# board.net
KiCad netlist of a schematic drawn in EAGLE
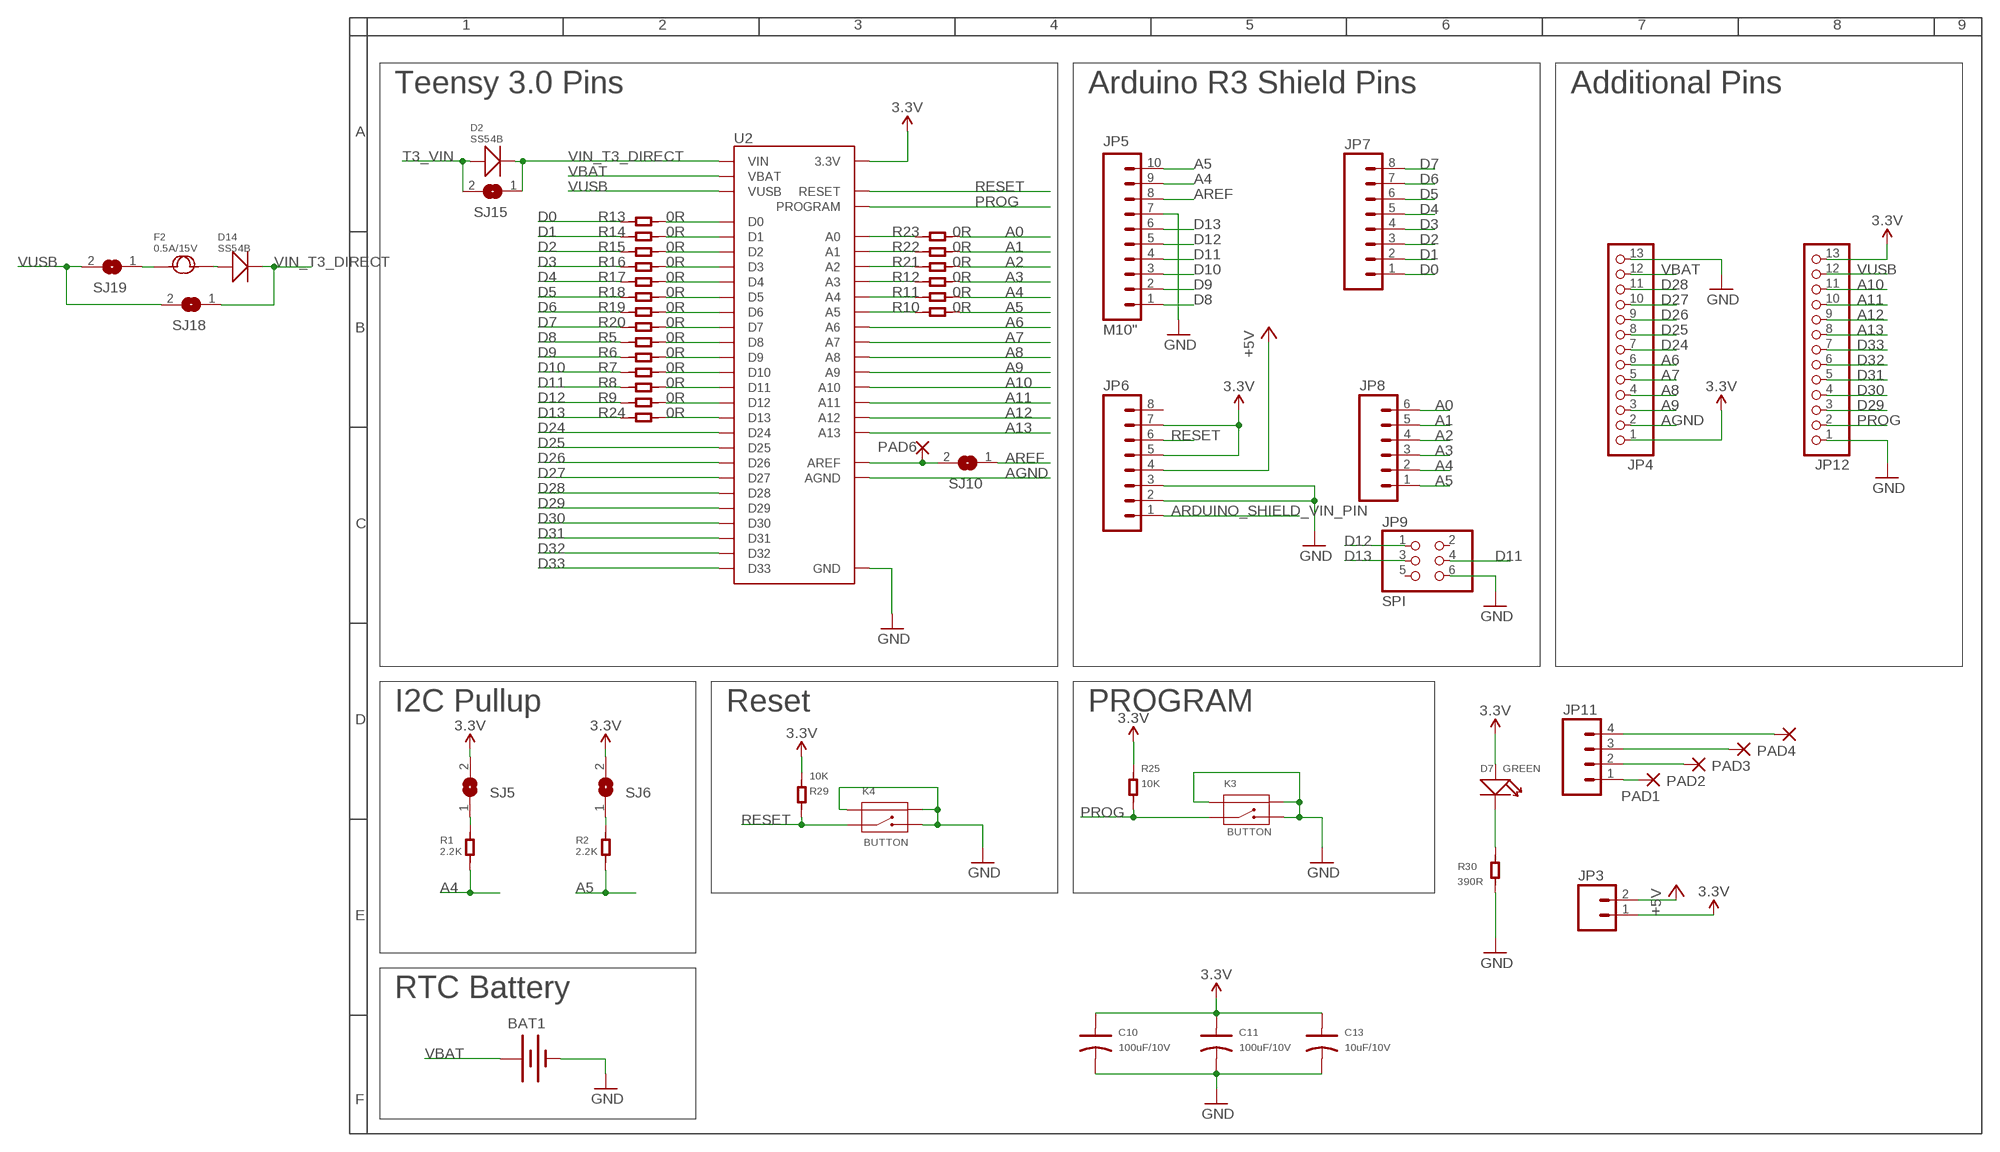
[diagram p0: schematic, sheet 1]
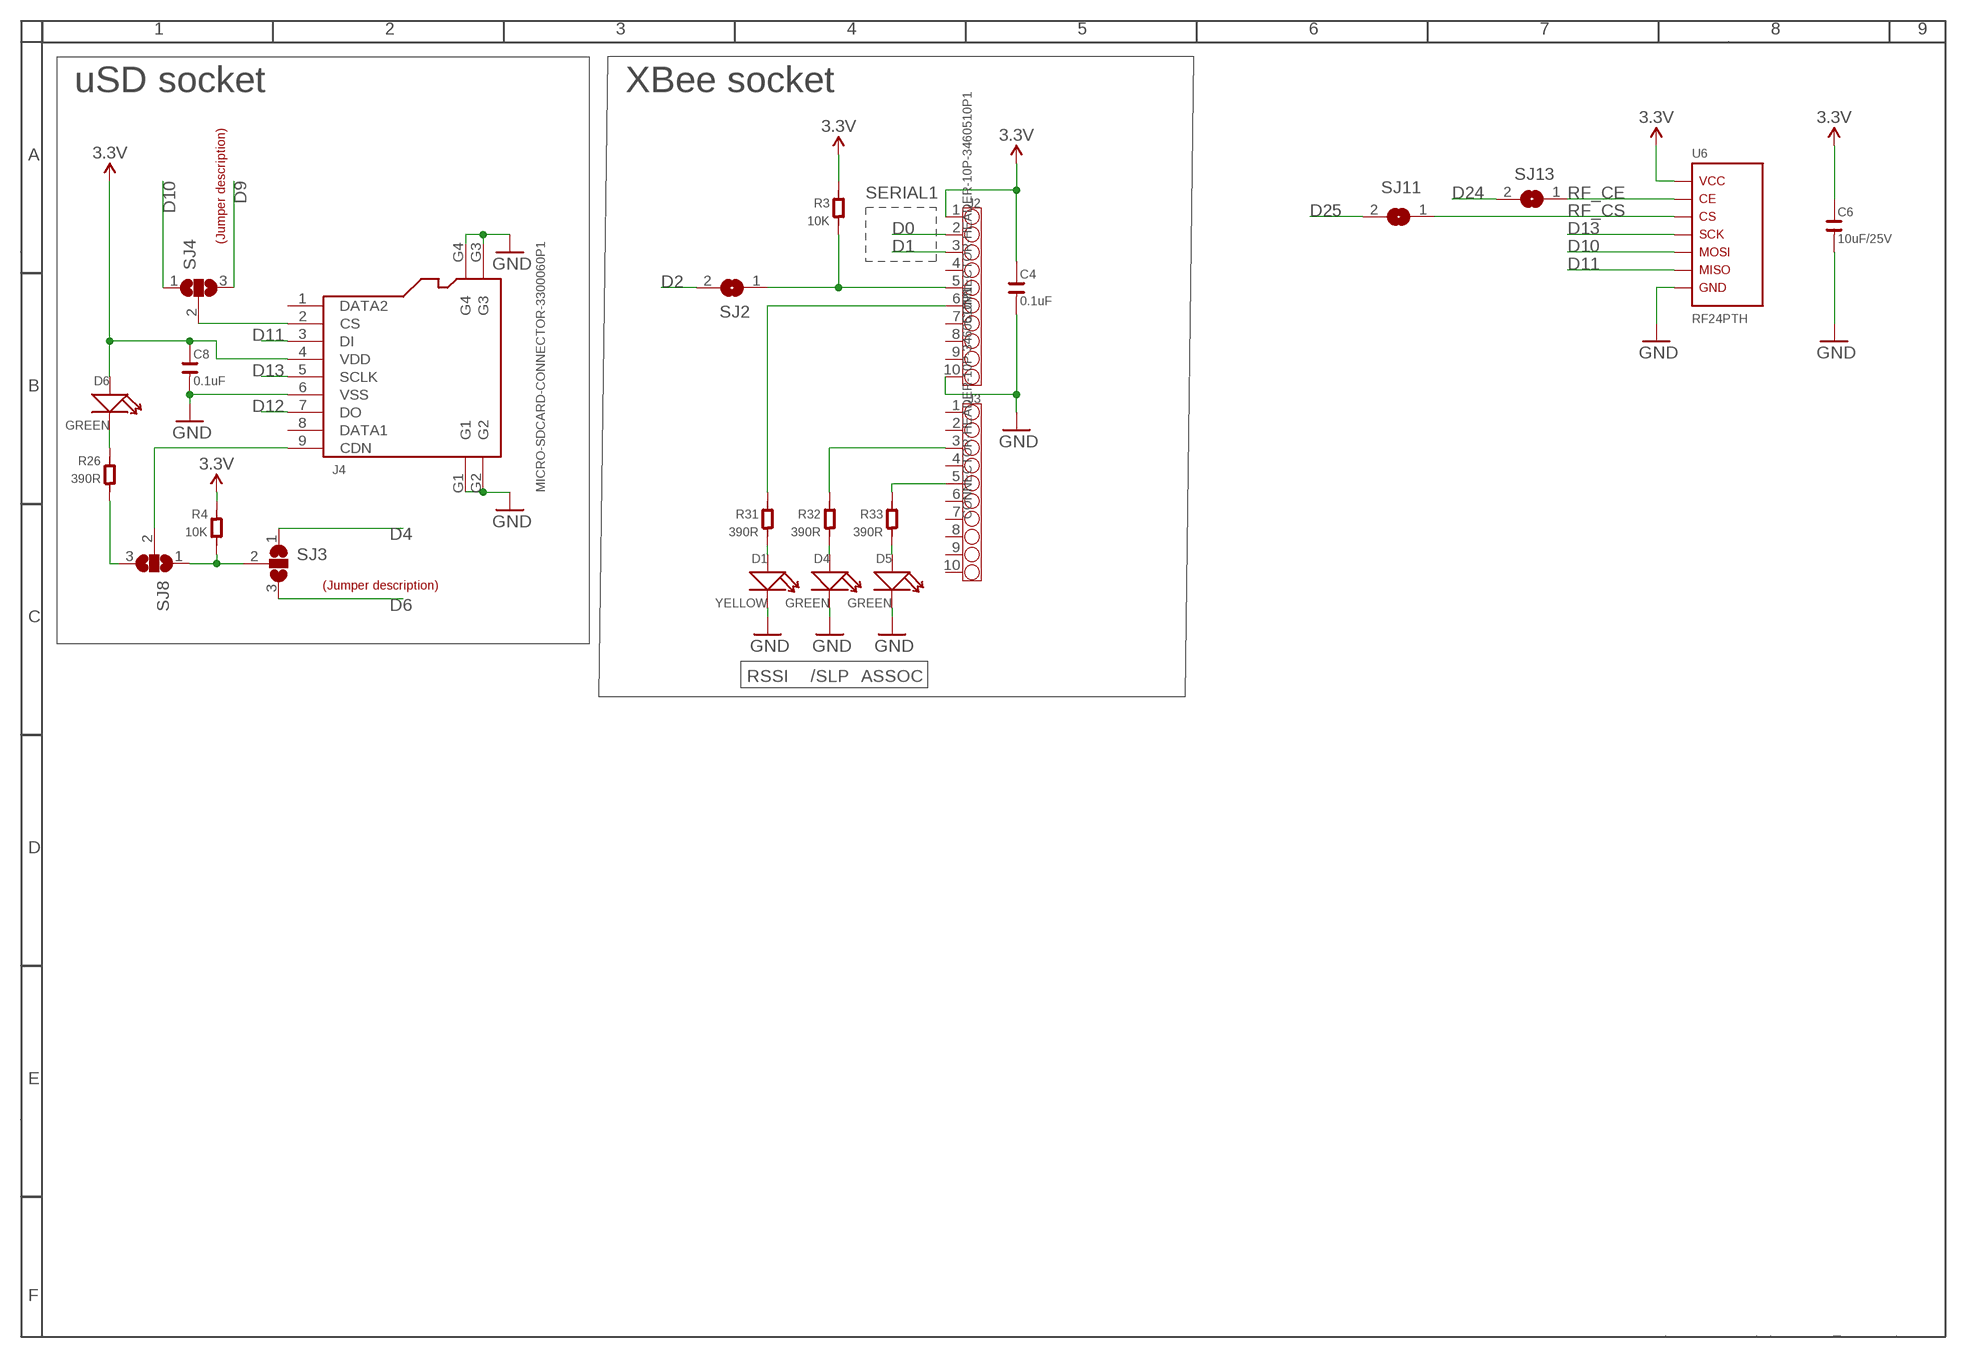
[diagram p1: schematic, sheet 2]
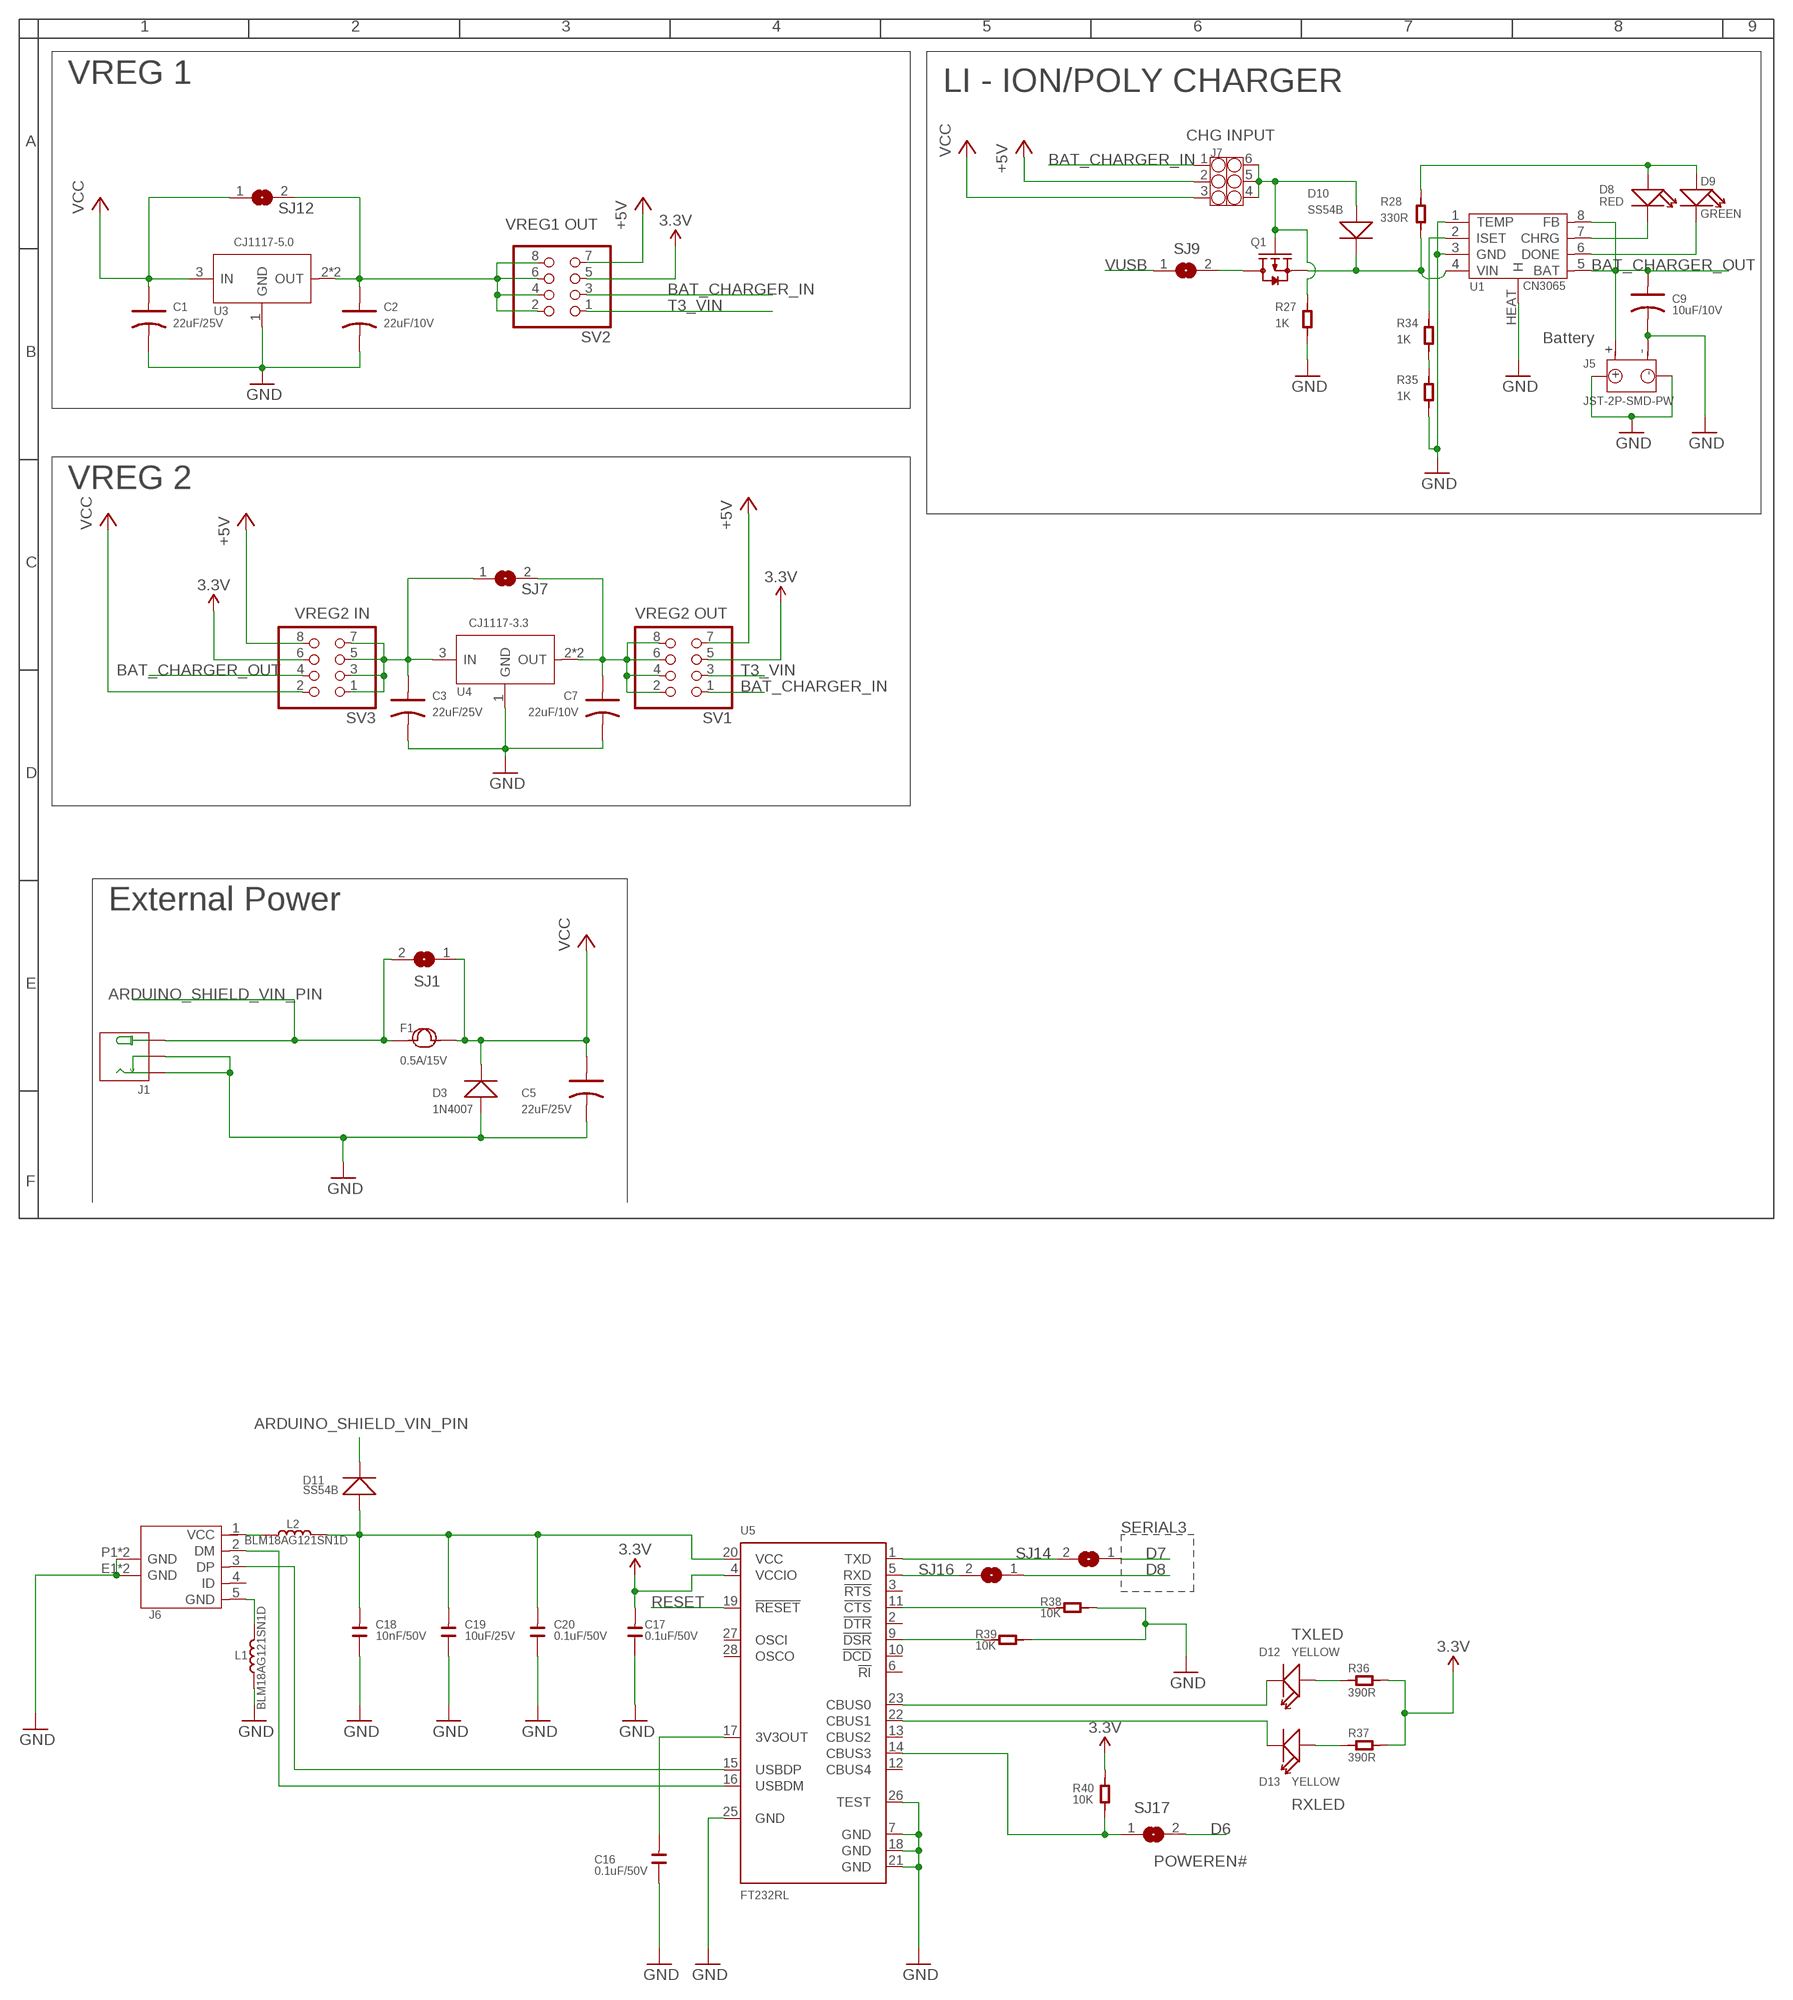
[diagram p2: schematic, sheet 3]

(export (version "E")
  (design (tool "Eeschema 10.0.6"))
  (components
    (comp (ref "C4")
      (value "0.1uF")
      (footprint "eagle-import:C0603")
      (libsource (lib "eagle-import") (part "C-0603"))
    )
    (comp (ref "C6")
      (value "10uF/25V")
      (footprint "eagle-import:C0805")
      (libsource (lib "eagle-import") (part "C-0805"))
    )
    (comp (ref "C8")
      (value "0.1uF")
      (footprint "eagle-import:C0603")
      (libsource (lib "eagle-import") (part "C-0603"))
    )
    (comp (ref "D1")
      (value "YELLOW")
      (footprint "eagle-import:LED0603")
      (libsource (lib "eagle-import") (part "LED"))
    )
    (comp (ref "D4")
      (value "GREEN")
      (footprint "eagle-import:LED0603")
      (libsource (lib "eagle-import") (part "LED"))
    )
    (comp (ref "D5")
      (value "GREEN")
      (footprint "eagle-import:LED0603")
      (libsource (lib "eagle-import") (part "LED"))
    )
    (comp (ref "D6")
      (value "GREEN")
      (footprint "eagle-import:LED0603")
      (libsource (lib "eagle-import") (part "LED"))
    )
    (comp (ref "J2")
      (value "CONNECTOR-HEADER-10P-3460510P1")
      (footprint "eagle-import:1X10P-2.0-4.3-BLUE-FEMALE")
      (libsource (lib "eagle-import") (part "CONNECTOR-HEADER-10P-3460510P1"))
    )
    (comp (ref "J3")
      (value "CONNECTOR-HEADER-10P-3460510P1")
      (footprint "eagle-import:1X10P-2.0-4.3-BLUE-FEMALE")
      (libsource (lib "eagle-import") (part "CONNECTOR-HEADER-10P-3460510P1"))
    )
    (comp (ref "J4")
      (value "MICRO-SDCARD-CONNECTOR-3300060P1")
      (footprint "eagle-import:9P-SMD-W-RING")
      (libsource (lib "eagle-import") (part "MICRO-SDCARD-CONNECTOR-3300060P1"))
    )
    (comp (ref "R3")
      (value "10K")
      (footprint "eagle-import:R0603")
      (libsource (lib "eagle-import") (part "R-0603"))
    )
    (comp (ref "R4")
      (value "10K")
      (footprint "eagle-import:R0603")
      (libsource (lib "eagle-import") (part "R-0603"))
    )
    (comp (ref "R26")
      (value "390R")
      (footprint "eagle-import:R0603")
      (libsource (lib "eagle-import") (part "R-0603"))
    )
    (comp (ref "R31")
      (value "390R")
      (footprint "eagle-import:R0603")
      (libsource (lib "eagle-import") (part "R-0603"))
    )
    (comp (ref "R32")
      (value "390R")
      (footprint "eagle-import:R0603")
      (libsource (lib "eagle-import") (part "R-0603"))
    )
    (comp (ref "R33")
      (value "390R")
      (footprint "eagle-import:R0603")
      (libsource (lib "eagle-import") (part "R-0603"))
    )
    (comp (ref "SJ2")
      (value "JUMPER_2WSMALL")
      (footprint "eagle-import:JUMPER_SMALL_2WAY")
      (libsource (lib "eagle-import") (part "JUMPER_2WSMALL"))
    )
    (comp (ref "SJ3")
      (value "SJ2W")
      (footprint "eagle-import:SJ_2")
      (libsource (lib "eagle-import") (part "SJ2W"))
    )
    (comp (ref "SJ4")
      (value "SJ2W")
      (footprint "eagle-import:SJ_2")
      (libsource (lib "eagle-import") (part "SJ2W"))
    )
    (comp (ref "SJ8")
      (value "SJ2W")
      (footprint "eagle-import:SJ_2")
      (libsource (lib "eagle-import") (part "SJ2W"))
    )
    (comp (ref "SJ11")
      (value "JUMPER_2WSMALL")
      (footprint "eagle-import:JUMPER_SMALL_2WAY")
      (libsource (lib "eagle-import") (part "JUMPER_2WSMALL"))
    )
    (comp (ref "SJ13")
      (value "JUMPER_2WSMALL")
      (footprint "eagle-import:JUMPER_SMALL_2WAY")
      (libsource (lib "eagle-import") (part "JUMPER_2WSMALL"))
    )
    (comp (ref "U$1")
      (value "LABEL_JUMPER_1X3")
      (footprint "eagle-import:JUMP3_DESC")
      (fields (field (name "LEFT") "D4") (field (name "RIGHT") "D6"))
      (libsource (lib "eagle-import") (part "LABEL_JUMPER_1X3"))
    )
    (comp (ref "U$2")
      (value "LABEL_JUMPER_1X3")
      (footprint "eagle-import:JUMP3_DESC")
      (fields (field (name "LEFT") "D9") (field (name "RIGHT") "D10"))
      (libsource (lib "eagle-import") (part "LABEL_JUMPER_1X3"))
    )
    (comp (ref "U6")
      (value "RF24PTH")
      (footprint "eagle-import:RF24")
      (libsource (lib "eagle-import") (part "RF24PTH"))
    )
    (comp (ref "BAT1")
      (value "BATTERY12MM")
      (footprint "eagle-import:BATTCON_12MM")
      (libsource (lib "eagle-import") (part "BATTERY12MM"))
    )
    (comp (ref "C10")
      (value "100uF/10V")
      (footprint "eagle-import:AVX-C")
      (libsource (lib "eagle-import") (part "C-POLAR-C"))
    )
    (comp (ref "C11")
      (value "100uF/10V")
      (footprint "eagle-import:AVX-C")
      (libsource (lib "eagle-import") (part "C-POLAR-C"))
    )
    (comp (ref "C13")
      (value "10uF/10V")
      (footprint "eagle-import:AVX-B")
      (libsource (lib "eagle-import") (part "C-POLAR-B"))
    )
    (comp (ref "D2")
      (value "SS54B")
      (footprint "eagle-import:SMB")
      (libsource (lib "eagle-import") (part "D-SMB"))
    )
    (comp (ref "D7")
      (value "GREEN")
      (footprint "eagle-import:LED0603")
      (libsource (lib "eagle-import") (part "LED"))
    )
    (comp (ref "D14")
      (value "SS54B")
      (footprint "eagle-import:SMB")
      (libsource (lib "eagle-import") (part "D-SMB"))
    )
    (comp (ref "F2")
      (value "0.5A/15V")
      (footprint "eagle-import:F1812")
      (libsource (lib "eagle-import") (part "OPL_20130807_FUSE-1812"))
    )
    (comp (ref "JP3")
      (value "M02PTH")
      (footprint "eagle-import:1X02")
      (libsource (lib "eagle-import") (part "M02PTH"))
    )
    (comp (ref "JP4")
      (value "PINHD-1X13_BIG")
      (footprint "eagle-import:1X13-BIG")
      (libsource (lib "eagle-import") (part "PINHD-1X13_BIG"))
    )
    (comp (ref "JP5")
      (value "M10\"")
      (footprint "eagle-import:1X10")
      (libsource (lib "eagle-import") (part "M10{dblquote}"))
    )
    (comp (ref "JP6")
      (value "M081X08")
      (footprint "eagle-import:1X08")
      (libsource (lib "eagle-import") (part "M081X08"))
    )
    (comp (ref "JP7")
      (value "M081X08")
      (footprint "eagle-import:1X08")
      (libsource (lib "eagle-import") (part "M081X08"))
    )
    (comp (ref "JP8")
      (value "M06SIP")
      (footprint "eagle-import:1X06")
      (libsource (lib "eagle-import") (part "M06SIP"))
    )
    (comp (ref "JP9")
      (value "SPI")
      (footprint "eagle-import:2X03")
      (libsource (lib "eagle-import") (part "PINHD-2X3"))
    )
    (comp (ref "JP11")
      (value "M04PTH")
      (footprint "eagle-import:1X04")
      (libsource (lib "eagle-import") (part "M04PTH"))
    )
    (comp (ref "JP12")
      (value "PINHD-1X13_BIG")
      (footprint "eagle-import:1X13-BIG")
      (libsource (lib "eagle-import") (part "PINHD-1X13_BIG"))
    )
    (comp (ref "K3")
      (value "BUTTON")
      (footprint "eagle-import:4P-SMD-7.0X3.5X3.5H-90D")
      (libsource (lib "eagle-import") (part "BUTTON-2P-REINFORCE-3100060P1"))
    )
    (comp (ref "K4")
      (value "BUTTON")
      (footprint "eagle-import:4P-SMD-7.0X3.5X3.5H-90D")
      (libsource (lib "eagle-import") (part "BUTTON-2P-REINFORCE-3100060P1"))
    )
    (comp (ref "PAD1")
      (value "WIREPADSMD1,27-254")
      (footprint "eagle-import:SMD1,27-2,54")
      (libsource (lib "eagle-import") (part "WIREPADSMD1,27-254"))
    )
    (comp (ref "PAD2")
      (value "WIREPADSMD1,27-254")
      (footprint "eagle-import:SMD1,27-2,54")
      (libsource (lib "eagle-import") (part "WIREPADSMD1,27-254"))
    )
    (comp (ref "PAD3")
      (value "WIREPADSMD1,27-254")
      (footprint "eagle-import:SMD1,27-2,54")
      (libsource (lib "eagle-import") (part "WIREPADSMD1,27-254"))
    )
    (comp (ref "PAD4")
      (value "WIREPADSMD1,27-254")
      (footprint "eagle-import:SMD1,27-2,54")
      (libsource (lib "eagle-import") (part "WIREPADSMD1,27-254"))
    )
    (comp (ref "PAD6")
      (value "AREF")
      (footprint "eagle-import:SMD1,27-2,54")
      (libsource (lib "eagle-import") (part "SMD2"))
    )
    (comp (ref "R1")
      (value "2.2K")
      (footprint "eagle-import:R0603")
      (libsource (lib "eagle-import") (part "R-0603"))
    )
    (comp (ref "R2")
      (value "2.2K")
      (footprint "eagle-import:R0603")
      (libsource (lib "eagle-import") (part "R-0603"))
    )
    (comp (ref "R5")
      (value "0R")
      (footprint "eagle-import:R0603")
      (libsource (lib "eagle-import") (part "R-0603"))
    )
    (comp (ref "R6")
      (value "0R")
      (footprint "eagle-import:R0603")
      (libsource (lib "eagle-import") (part "R-0603"))
    )
    (comp (ref "R7")
      (value "0R")
      (footprint "eagle-import:R0603")
      (libsource (lib "eagle-import") (part "R-0603"))
    )
    (comp (ref "R8")
      (value "0R")
      (footprint "eagle-import:R0603")
      (libsource (lib "eagle-import") (part "R-0603"))
    )
    (comp (ref "R9")
      (value "0R")
      (footprint "eagle-import:R0603")
      (libsource (lib "eagle-import") (part "R-0603"))
    )
    (comp (ref "R10")
      (value "0R")
      (footprint "eagle-import:R0603")
      (libsource (lib "eagle-import") (part "R-0603"))
    )
    (comp (ref "R11")
      (value "0R")
      (footprint "eagle-import:R0603")
      (libsource (lib "eagle-import") (part "R-0603"))
    )
    (comp (ref "R12")
      (value "0R")
      (footprint "eagle-import:R0603")
      (libsource (lib "eagle-import") (part "R-0603"))
    )
    (comp (ref "R13")
      (value "0R")
      (footprint "eagle-import:R0603")
      (libsource (lib "eagle-import") (part "R-0603"))
    )
    (comp (ref "R14")
      (value "0R")
      (footprint "eagle-import:R0603")
      (libsource (lib "eagle-import") (part "R-0603"))
    )
    (comp (ref "R15")
      (value "0R")
      (footprint "eagle-import:R0603")
      (libsource (lib "eagle-import") (part "R-0603"))
    )
    (comp (ref "R16")
      (value "0R")
      (footprint "eagle-import:R0603")
      (libsource (lib "eagle-import") (part "R-0603"))
    )
    (comp (ref "R17")
      (value "0R")
      (footprint "eagle-import:R0603")
      (libsource (lib "eagle-import") (part "R-0603"))
    )
    (comp (ref "R18")
      (value "0R")
      (footprint "eagle-import:R0603")
      (libsource (lib "eagle-import") (part "R-0603"))
    )
    (comp (ref "R19")
      (value "0R")
      (footprint "eagle-import:R0603")
      (libsource (lib "eagle-import") (part "R-0603"))
    )
    (comp (ref "R20")
      (value "0R")
      (footprint "eagle-import:R0603")
      (libsource (lib "eagle-import") (part "R-0603"))
    )
    (comp (ref "R21")
      (value "0R")
      (footprint "eagle-import:R0603")
      (libsource (lib "eagle-import") (part "R-0603"))
    )
    (comp (ref "R22")
      (value "0R")
      (footprint "eagle-import:R0603")
      (libsource (lib "eagle-import") (part "R-0603"))
    )
    (comp (ref "R23")
      (value "0R")
      (footprint "eagle-import:R0603")
      (libsource (lib "eagle-import") (part "R-0603"))
    )
    (comp (ref "R24")
      (value "0R")
      (footprint "eagle-import:R0603")
      (libsource (lib "eagle-import") (part "R-0603"))
    )
    (comp (ref "R25")
      (value "10K")
      (footprint "eagle-import:R0603")
      (libsource (lib "eagle-import") (part "R-0603"))
    )
    (comp (ref "R29")
      (value "10K")
      (footprint "eagle-import:R0603")
      (libsource (lib "eagle-import") (part "R-0603"))
    )
    (comp (ref "R30")
      (value "390R")
      (footprint "eagle-import:R0603")
      (libsource (lib "eagle-import") (part "R-0603"))
    )
    (comp (ref "SJ5")
      (value "JUMPER_2WLARGE")
      (footprint "eagle-import:JUMPER_LARGE_2WAY")
      (libsource (lib "eagle-import") (part "JUMPER_2WLARGE"))
    )
    (comp (ref "SJ6")
      (value "JUMPER_2WLARGE")
      (footprint "eagle-import:JUMPER_LARGE_2WAY")
      (libsource (lib "eagle-import") (part "JUMPER_2WLARGE"))
    )
    (comp (ref "SJ10")
      (value "JUMPER_2WLARGE")
      (footprint "eagle-import:JUMPER_LARGE_2WAY")
      (libsource (lib "eagle-import") (part "JUMPER_2WLARGE"))
    )
    (comp (ref "SJ15")
      (value "JUMPER_2WLARGE")
      (footprint "eagle-import:JUMPER_LARGE_2WAY")
      (libsource (lib "eagle-import") (part "JUMPER_2WLARGE"))
    )
    (comp (ref "SJ18")
      (value "JUMPER_2WLARGE")
      (footprint "eagle-import:JUMPER_LARGE_2WAY")
      (libsource (lib "eagle-import") (part "JUMPER_2WLARGE"))
    )
    (comp (ref "SJ19")
      (value "JUMPER_2WLARGE")
      (footprint "eagle-import:JUMPER_LARGE_2WAY")
      (libsource (lib "eagle-import") (part "JUMPER_2WLARGE"))
    )
    (comp (ref "U2")
      (value "TEENSY3.0_ALLPINSSILK")
      (footprint "eagle-import:TEENSY3.0_ALLPINS_SILK")
      (libsource (lib "eagle-import") (part "TEENSY3.0_ALLPINSSILK"))
    )
    (comp (ref "C1")
      (value "22uF/25V")
      (footprint "eagle-import:AVX-C")
      (fields (field (name "MPN") "TAJC226K025RNJ"))
      (libsource (lib "eagle-import") (part "C-POLAR-C"))
    )
    (comp (ref "C2")
      (value "22uF/10V")
      (footprint "eagle-import:AVX-B")
      (libsource (lib "eagle-import") (part "C-POLAR-B"))
    )
    (comp (ref "C3")
      (value "22uF/25V")
      (footprint "eagle-import:AVX-C")
      (fields (field (name "MPN") "TAJC226K025RNJ"))
      (libsource (lib "eagle-import") (part "C-POLAR-C"))
    )
    (comp (ref "C5")
      (value "22uF/25V")
      (footprint "eagle-import:AVX-C")
      (libsource (lib "eagle-import") (part "C-POLAR-C"))
    )
    (comp (ref "C7")
      (value "22uF/10V")
      (footprint "eagle-import:AVX-B")
      (libsource (lib "eagle-import") (part "C-POLAR-B"))
    )
    (comp (ref "C9")
      (value "10uF/10V")
      (footprint "eagle-import:AVX-A")
      (libsource (lib "eagle-import") (part "C-POLAR-A"))
    )
    (comp (ref "C16")
      (value "0.1uF/50V")
      (footprint "eagle-import:C0603")
      (libsource (lib "eagle-import") (part "C-0603"))
    )
    (comp (ref "C17")
      (value "0.1uF/50V")
      (footprint "eagle-import:C0603")
      (libsource (lib "eagle-import") (part "C-0603"))
    )
    (comp (ref "C18")
      (value "10nF/50V")
      (footprint "eagle-import:C0603")
      (libsource (lib "eagle-import") (part "C-0603"))
    )
    (comp (ref "C19")
      (value "10uF/25V")
      (footprint "eagle-import:C0805")
      (libsource (lib "eagle-import") (part "C-0805"))
    )
    (comp (ref "C20")
      (value "0.1uF/50V")
      (footprint "eagle-import:C0603")
      (libsource (lib "eagle-import") (part "C-0603"))
    )
    (comp (ref "D3")
      (value "1N4007")
      (footprint "eagle-import:DO-214AC")
      (libsource (lib "eagle-import") (part "D-SMA"))
    )
    (comp (ref "D8")
      (value "RED")
      (footprint "eagle-import:LED0603")
      (libsource (lib "eagle-import") (part "LED"))
    )
    (comp (ref "D9")
      (value "GREEN")
      (footprint "eagle-import:LED0603")
      (libsource (lib "eagle-import") (part "LED"))
    )
    (comp (ref "D10")
      (value "SS54B")
      (footprint "eagle-import:SMB")
      (libsource (lib "eagle-import") (part "D-SMB"))
    )
    (comp (ref "D11")
      (value "SS54B")
      (footprint "eagle-import:SMB")
      (libsource (lib "eagle-import") (part "D-SMB"))
    )
    (comp (ref "D12")
      (value "YELLOW")
      (footprint "eagle-import:LED0603")
      (libsource (lib "eagle-import") (part "LED"))
    )
    (comp (ref "D13")
      (value "YELLOW")
      (footprint "eagle-import:LED0603")
      (libsource (lib "eagle-import") (part "LED"))
    )
    (comp (ref "F1")
      (value "0.5A/15V")
      (footprint "eagle-import:F1812")
      (libsource (lib "eagle-import") (part "FUSE-1812"))
    )
    (comp (ref "J1")
      (value "JACK-DC-3P-3410020P1")
      (footprint "eagle-import:PW-3P-2.1")
      (libsource (lib "eagle-import") (part "JACK-DC-3P-3410020P1"))
    )
    (comp (ref "J5")
      (value "JST-2P-SMD-PW")
      (footprint "eagle-import:2P-SMD-2.0-90D")
      (libsource (lib "eagle-import") (part "JST-2P-SMD-PW-3410050P1"))
    )
    (comp (ref "J6")
      (value "MICRO-USB-5P-3400150P1")
      (footprint "eagle-import:B-SMD-5P")
      (libsource (lib "eagle-import") (part "MICRO-USB-5P-3400150P1"))
    )
    (comp (ref "J7")
      (value "CONNECTOR-HEADER-2X3P-3460180P1")
      (footprint "eagle-import:2X3P-2.54-2.54-11.6-3.0-BLACK-MALE")
      (libsource (lib "eagle-import") (part "CONNECTOR-HEADER-2X3P-3460180P1"))
    )
    (comp (ref "L1")
      (value "BLM18AG121SN1D")
      (footprint "eagle-import:L0603")
      (libsource (lib "eagle-import") (part "L-0603"))
    )
    (comp (ref "L2")
      (value "BLM18AG121SN1D")
      (footprint "eagle-import:L0603")
      (libsource (lib "eagle-import") (part "L-0603"))
    )
    (comp (ref "Q1")
      (value "MOSFET-P-0440210P1")
      (footprint "eagle-import:SOT23")
      (libsource (lib "eagle-import") (part "MOSFET-P-0440210P1"))
    )
    (comp (ref "R27")
      (value "1K")
      (footprint "eagle-import:R0603")
      (libsource (lib "eagle-import") (part "R-0603"))
    )
    (comp (ref "R28")
      (value "330R")
      (footprint "eagle-import:R0603")
      (libsource (lib "eagle-import") (part "R-0603"))
    )
    (comp (ref "R34")
      (value "1K")
      (footprint "eagle-import:R0603")
      (libsource (lib "eagle-import") (part "R-0603"))
    )
    (comp (ref "R35")
      (value "1K")
      (footprint "eagle-import:R0603")
      (libsource (lib "eagle-import") (part "R-0603"))
    )
    (comp (ref "R36")
      (value "390R")
      (footprint "eagle-import:R0603")
      (libsource (lib "eagle-import") (part "R-0603"))
    )
    (comp (ref "R37")
      (value "390R")
      (footprint "eagle-import:R0603")
      (libsource (lib "eagle-import") (part "R-0603"))
    )
    (comp (ref "R38")
      (value "10K")
      (footprint "eagle-import:R0603")
      (libsource (lib "eagle-import") (part "R-0603"))
    )
    (comp (ref "R39")
      (value "10K")
      (footprint "eagle-import:R0603")
      (libsource (lib "eagle-import") (part "R-0603"))
    )
    (comp (ref "R40")
      (value "10K")
      (footprint "eagle-import:R0603")
      (libsource (lib "eagle-import") (part "R-0603"))
    )
    (comp (ref "SJ1")
      (value "JUMPER_2WLARGE")
      (footprint "eagle-import:JUMPER_LARGE_2WAY")
      (libsource (lib "eagle-import") (part "JUMPER_2WLARGE"))
    )
    (comp (ref "SJ7")
      (value "JUMPER_2WLARGE")
      (footprint "eagle-import:JUMPER_LARGE_2WAY")
      (libsource (lib "eagle-import") (part "JUMPER_2WLARGE"))
    )
    (comp (ref "SJ9")
      (value "JUMPER_2WLARGE")
      (footprint "eagle-import:JUMPER_LARGE_2WAY")
      (libsource (lib "eagle-import") (part "JUMPER_2WLARGE"))
    )
    (comp (ref "SJ12")
      (value "JUMPER_2WLARGE")
      (footprint "eagle-import:JUMPER_LARGE_2WAY")
      (libsource (lib "eagle-import") (part "JUMPER_2WLARGE"))
    )
    (comp (ref "SJ14")
      (value "JUMPER_2WLARGE")
      (footprint "eagle-import:JUMPER_LARGE_2WAY")
      (libsource (lib "eagle-import") (part "JUMPER_2WLARGE"))
    )
    (comp (ref "SJ16")
      (value "JUMPER_2WLARGE")
      (footprint "eagle-import:JUMPER_LARGE_2WAY")
      (libsource (lib "eagle-import") (part "JUMPER_2WLARGE"))
    )
    (comp (ref "SJ17")
      (value "JUMPER_2WLARGE")
      (footprint "eagle-import:JUMPER_LARGE_2WAY")
      (libsource (lib "eagle-import") (part "JUMPER_2WLARGE"))
    )
    (comp (ref "SV1")
      (value "PINHD-2X4_2.54")
      (footprint "eagle-import:2X04")
      (libsource (lib "eagle-import") (part "PINHD-2X4_2.54"))
    )
    (comp (ref "SV2")
      (value "PINHD-2X4_2.54")
      (footprint "eagle-import:2X04")
      (libsource (lib "eagle-import") (part "PINHD-2X4_2.54"))
    )
    (comp (ref "SV3")
      (value "PINHD-2X4_2.54")
      (footprint "eagle-import:2X04")
      (libsource (lib "eagle-import") (part "PINHD-2X4_2.54"))
    )
    (comp (ref "U1")
      (value "CN3065")
      (footprint "eagle-import:DFN8")
      (libsource (lib "eagle-import") (part "CN3065-1320040P1"))
    )
    (comp (ref "U3")
      (value "CJ1117-5.0")
      (footprint "eagle-import:SOT223")
      (libsource (lib "eagle-import") (part "CJ1117-5.0-1310170P1"))
    )
    (comp (ref "U4")
      (value "CJ1117-3.3")
      (footprint "eagle-import:SOT223")
      (libsource (lib "eagle-import") (part "CJ1117-3.3-1310190P1"))
    )
    (comp (ref "U5")
      (value "FT232RL")
      (footprint "eagle-import:SSOP28")
      (libsource (lib "eagle-import") (part "FT232RL-1720010P1"))
    )
  )
  (nets
    (net (code "1") (name "+5V") (class "Default")
      (node (ref "J7") (pin "2") (pinfunction "2_2") (pintype "bidirectional"))
      (node (ref "JP3") (pin "2") (pinfunction "2_2") (pintype "passive"))
      (node (ref "JP6") (pin "4") (pinfunction "4_4") (pintype "passive"))
      (node (ref "SV1") (pin "7") (pinfunction "7_7") (pintype "passive"))
      (node (ref "SV2") (pin "7") (pinfunction "7_7") (pintype "passive"))
      (node (ref "SV3") (pin "8") (pinfunction "8_8") (pintype "passive"))
    )
    (net (code "2") (name "3.3V") (class "Default")
      (node (ref "C10") (pin "+") (pinfunction "1_+") (pintype "bidirectional"))
      (node (ref "C11") (pin "+") (pinfunction "1_+") (pintype "bidirectional"))
      (node (ref "C13") (pin "+") (pinfunction "1_+") (pintype "bidirectional"))
      (node (ref "C17") (pin "1") (pinfunction "1_1") (pintype "bidirectional"))
      (node (ref "C4") (pin "2") (pinfunction "2_2") (pintype "bidirectional"))
      (node (ref "C6") (pin "2") (pinfunction "2_2") (pintype "bidirectional"))
      (node (ref "C8") (pin "2") (pinfunction "2_2") (pintype "bidirectional"))
      (node (ref "D6") (pin "+") (pinfunction "+_+") (pintype "passive"))
      (node (ref "D7") (pin "+") (pinfunction "+_+") (pintype "passive"))
      (node (ref "J2") (pin "1") (pinfunction "1_1") (pintype "bidirectional"))
      (node (ref "J4") (pin "4") (pinfunction "VDD_4") (pintype "bidirectional"))
      (node (ref "JP12") (pin "13") (pinfunction "13_13") (pintype "passive"))
      (node (ref "JP3") (pin "1") (pinfunction "1_1") (pintype "passive"))
      (node (ref "JP4") (pin "1") (pinfunction "1_1") (pintype "passive"))
      (node (ref "JP6") (pin "5") (pinfunction "5_5") (pintype "passive"))
      (node (ref "JP6") (pin "7") (pinfunction "7_7") (pintype "passive"))
      (node (ref "R25") (pin "2") (pinfunction "2_2") (pintype "bidirectional"))
      (node (ref "R29") (pin "2") (pinfunction "2_2") (pintype "bidirectional"))
      (node (ref "R3") (pin "2") (pinfunction "2_2") (pintype "bidirectional"))
      (node (ref "R36") (pin "2") (pinfunction "2_2") (pintype "bidirectional"))
      (node (ref "R37") (pin "2") (pinfunction "2_2") (pintype "bidirectional"))
      (node (ref "R4") (pin "1") (pinfunction "1_1") (pintype "bidirectional"))
      (node (ref "R40") (pin "2") (pinfunction "2_2") (pintype "bidirectional"))
      (node (ref "SJ5") (pin "2") (pinfunction "2_2") (pintype "passive"))
      (node (ref "SJ6") (pin "2") (pinfunction "2_2") (pintype "passive"))
      (node (ref "SV1") (pin "5") (pinfunction "5_5") (pintype "passive"))
      (node (ref "SV2") (pin "5") (pinfunction "5_5") (pintype "passive"))
      (node (ref "SV3") (pin "6") (pinfunction "6_6") (pintype "passive"))
      (node (ref "U2") (pin "3V3_A") (pinfunction "3.3V_3V3_A") (pintype "power_in"))
      (node (ref "U2") (pin "3V3_B") (pinfunction "3.3V_3V3_B") (pintype "power_in"))
      (node (ref "U2") (pin "3V3_C") (pinfunction "3.3V_3V3_C") (pintype "power_in"))
      (node (ref "U5") (pin "4") (pinfunction "VCCIO_4") (pintype "input"))
      (node (ref "U6") (pin "VCC") (pinfunction "VCC_VCC") (pintype "power_in"))
    )
    (net (code "3") (name "A0") (class "Default")
      (node (ref "JP8") (pin "6") (pinfunction "6_6") (pintype "passive"))
      (node (ref "R23") (pin "1") (pinfunction "1_1") (pintype "bidirectional"))
    )
    (net (code "4") (name "A1") (class "Default")
      (node (ref "JP8") (pin "5") (pinfunction "5_5") (pintype "passive"))
      (node (ref "R22") (pin "1") (pinfunction "1_1") (pintype "bidirectional"))
    )
    (net (code "5") (name "A2") (class "Default")
      (node (ref "JP8") (pin "4") (pinfunction "4_4") (pintype "passive"))
      (node (ref "R21") (pin "1") (pinfunction "1_1") (pintype "bidirectional"))
    )
    (net (code "6") (name "A3") (class "Default")
      (node (ref "JP8") (pin "3") (pinfunction "3_3") (pintype "passive"))
      (node (ref "R12") (pin "1") (pinfunction "1_1") (pintype "bidirectional"))
    )
    (net (code "7") (name "A4") (class "Default")
      (node (ref "JP5") (pin "9") (pinfunction "9_9") (pintype "passive"))
      (node (ref "JP8") (pin "2") (pinfunction "2_2") (pintype "passive"))
      (node (ref "R1") (pin "1") (pinfunction "1_1") (pintype "bidirectional"))
      (node (ref "R11") (pin "1") (pinfunction "1_1") (pintype "bidirectional"))
    )
    (net (code "8") (name "A5") (class "Default")
      (node (ref "JP5") (pin "10") (pinfunction "10_10") (pintype "passive"))
      (node (ref "JP8") (pin "1") (pinfunction "1_1") (pintype "passive"))
      (node (ref "R10") (pin "1") (pinfunction "1_1") (pintype "bidirectional"))
      (node (ref "R2") (pin "1") (pinfunction "1_1") (pintype "bidirectional"))
    )
    (net (code "9") (name "A6") (class "Default")
      (node (ref "JP4") (pin "6") (pinfunction "6_6") (pintype "passive"))
      (node (ref "U2") (pin "A6") (pinfunction "A6_A6") (pintype "bidirectional"))
    )
    (net (code "10") (name "A7") (class "Default")
      (node (ref "JP4") (pin "5") (pinfunction "5_5") (pintype "passive"))
      (node (ref "U2") (pin "A7") (pinfunction "A7_A7") (pintype "bidirectional"))
    )
    (net (code "11") (name "A8") (class "Default")
      (node (ref "JP4") (pin "4") (pinfunction "4_4") (pintype "passive"))
      (node (ref "U2") (pin "A8") (pinfunction "A8_A8") (pintype "bidirectional"))
    )
    (net (code "12") (name "A9") (class "Default")
      (node (ref "JP4") (pin "3") (pinfunction "3_3") (pintype "passive"))
      (node (ref "U2") (pin "A9") (pinfunction "A9_A9") (pintype "bidirectional"))
    )
    (net (code "13") (name "A10") (class "Default")
      (node (ref "JP12") (pin "11") (pinfunction "11_11") (pintype "passive"))
      (node (ref "U2") (pin "A10") (pinfunction "A10_A10") (pintype "bidirectional"))
    )
    (net (code "14") (name "A11") (class "Default")
      (node (ref "JP12") (pin "10") (pinfunction "10_10") (pintype "passive"))
      (node (ref "U2") (pin "A11") (pinfunction "A11_A11") (pintype "bidirectional"))
    )
    (net (code "15") (name "A12") (class "Default")
      (node (ref "JP12") (pin "9") (pinfunction "9_9") (pintype "passive"))
      (node (ref "U2") (pin "A12") (pinfunction "A12_A12") (pintype "bidirectional"))
    )
    (net (code "16") (name "A13") (class "Default")
      (node (ref "JP12") (pin "8") (pinfunction "8_8") (pintype "passive"))
      (node (ref "U2") (pin "A13") (pinfunction "A13_A13") (pintype "bidirectional"))
    )
    (net (code "17") (name "AGND") (class "Default")
      (node (ref "JP4") (pin "2") (pinfunction "2_2") (pintype "passive"))
      (node (ref "U2") (pin "AGND") (pinfunction "AGND_AGND") (pintype "bidirectional"))
    )
    (net (code "18") (name "ARDUINO_SHIELD_VIN_PIN") (class "Default")
      (node (ref "D11") (pin "-") (pinfunction "-_-") (pintype "passive"))
      (node (ref "F1") (pin "1") (pinfunction "1_1") (pintype "bidirectional"))
      (node (ref "J1") (pin "+") (pinfunction "+_+") (pintype "bidirectional"))
      (node (ref "JP6") (pin "1") (pinfunction "1_1") (pintype "passive"))
      (node (ref "SJ1") (pin "2") (pinfunction "2_2") (pintype "passive"))
    )
    (net (code "19") (name "AREF") (class "Default")
      (node (ref "JP5") (pin "8") (pinfunction "8_8") (pintype "passive"))
      (node (ref "SJ10") (pin "1") (pinfunction "1_1") (pintype "passive"))
    )
    (net (code "20") (name "BAT_CHARGER_IN") (class "Default")
      (node (ref "J7") (pin "1") (pinfunction "1_1") (pintype "bidirectional"))
      (node (ref "SV1") (pin "1") (pinfunction "1_1") (pintype "passive"))
      (node (ref "SV2") (pin "3") (pinfunction "3_3") (pintype "passive"))
    )
    (net (code "21") (name "BAT_CHARGER_OUT") (class "Default")
      (node (ref "C9") (pin "+") (pinfunction "1_+") (pintype "bidirectional"))
      (node (ref "J5") (pin "+") (pinfunction "+_+") (pintype "bidirectional"))
      (node (ref "SV3") (pin "4") (pinfunction "4_4") (pintype "passive"))
      (node (ref "U1") (pin "5") (pinfunction "BAT_5") (pintype "bidirectional"))
      (node (ref "U1") (pin "8") (pinfunction "FB_8") (pintype "input"))
    )
    (net (code "22") (name "D0") (class "Default")
      (node (ref "J2") (pin "2") (pinfunction "2_2") (pintype "bidirectional"))
      (node (ref "JP7") (pin "1") (pinfunction "1_1") (pintype "passive"))
      (node (ref "R13") (pin "2") (pinfunction "2_2") (pintype "bidirectional"))
    )
    (net (code "23") (name "D1") (class "Default")
      (node (ref "J2") (pin "3") (pinfunction "3_3") (pintype "bidirectional"))
      (node (ref "JP7") (pin "2") (pinfunction "2_2") (pintype "passive"))
      (node (ref "R14") (pin "2") (pinfunction "2_2") (pintype "bidirectional"))
    )
    (net (code "24") (name "D2") (class "Default")
      (node (ref "JP7") (pin "3") (pinfunction "3_3") (pintype "passive"))
      (node (ref "R15") (pin "2") (pinfunction "2_2") (pintype "bidirectional"))
      (node (ref "SJ2") (pin "2") (pinfunction "2_2") (pintype "passive"))
    )
    (net (code "25") (name "D3") (class "Default")
      (node (ref "JP7") (pin "4") (pinfunction "4_4") (pintype "passive"))
      (node (ref "R16") (pin "2") (pinfunction "2_2") (pintype "bidirectional"))
    )
    (net (code "26") (name "D4") (class "Default")
      (node (ref "JP7") (pin "5") (pinfunction "5_5") (pintype "passive"))
      (node (ref "R17") (pin "2") (pinfunction "2_2") (pintype "bidirectional"))
      (node (ref "SJ3") (pin "1") (pinfunction "1_1") (pintype "passive"))
    )
    (net (code "27") (name "D5") (class "Default")
      (node (ref "JP7") (pin "6") (pinfunction "6_6") (pintype "passive"))
      (node (ref "R18") (pin "2") (pinfunction "2_2") (pintype "bidirectional"))
    )
    (net (code "28") (name "D6") (class "Default")
      (node (ref "JP7") (pin "7") (pinfunction "7_7") (pintype "passive"))
      (node (ref "R19") (pin "2") (pinfunction "2_2") (pintype "bidirectional"))
      (node (ref "SJ17") (pin "2") (pinfunction "2_2") (pintype "passive"))
      (node (ref "SJ3") (pin "3") (pinfunction "3_3") (pintype "passive"))
    )
    (net (code "29") (name "D7") (class "Default")
      (node (ref "JP7") (pin "8") (pinfunction "8_8") (pintype "passive"))
      (node (ref "R20") (pin "2") (pinfunction "2_2") (pintype "bidirectional"))
      (node (ref "SJ14") (pin "1") (pinfunction "1_1") (pintype "passive"))
    )
    (net (code "30") (name "D8") (class "Default")
      (node (ref "JP5") (pin "1") (pinfunction "1_1") (pintype "passive"))
      (node (ref "R5") (pin "2") (pinfunction "2_2") (pintype "bidirectional"))
      (node (ref "SJ16") (pin "1") (pinfunction "1_1") (pintype "passive"))
    )
    (net (code "31") (name "D9") (class "Default")
      (node (ref "JP5") (pin "2") (pinfunction "2_2") (pintype "passive"))
      (node (ref "R6") (pin "2") (pinfunction "2_2") (pintype "bidirectional"))
      (node (ref "SJ4") (pin "3") (pinfunction "3_3") (pintype "passive"))
    )
    (net (code "32") (name "D10") (class "Default")
      (node (ref "JP5") (pin "3") (pinfunction "3_3") (pintype "passive"))
      (node (ref "R7") (pin "2") (pinfunction "2_2") (pintype "bidirectional"))
      (node (ref "SJ4") (pin "1") (pinfunction "1_1") (pintype "passive"))
      (node (ref "U6") (pin "MOSI") (pinfunction "MOSI_MOSI") (pintype "input"))
    )
    (net (code "33") (name "D11") (class "Default")
      (node (ref "J4") (pin "3") (pinfunction "DI_3") (pintype "bidirectional"))
      (node (ref "JP5") (pin "4") (pinfunction "4_4") (pintype "passive"))
      (node (ref "JP9") (pin "4") (pinfunction "4_4") (pintype "passive"))
      (node (ref "R8") (pin "2") (pinfunction "2_2") (pintype "bidirectional"))
      (node (ref "U6") (pin "MISO") (pinfunction "MISO_MISO") (pintype "output"))
    )
    (net (code "34") (name "D12") (class "Default")
      (node (ref "J4") (pin "7") (pinfunction "DO_7") (pintype "bidirectional"))
      (node (ref "JP5") (pin "5") (pinfunction "5_5") (pintype "passive"))
      (node (ref "JP9") (pin "1") (pinfunction "1_1") (pintype "passive"))
      (node (ref "R9") (pin "2") (pinfunction "2_2") (pintype "bidirectional"))
    )
    (net (code "35") (name "D13") (class "Default")
      (node (ref "J4") (pin "5") (pinfunction "SCLK_5") (pintype "bidirectional"))
      (node (ref "JP5") (pin "6") (pinfunction "6_6") (pintype "passive"))
      (node (ref "JP9") (pin "3") (pinfunction "3_3") (pintype "passive"))
      (node (ref "R24") (pin "2") (pinfunction "2_2") (pintype "bidirectional"))
      (node (ref "U6") (pin "SCK") (pinfunction "SCK_SCK") (pintype "input"))
    )
    (net (code "36") (name "D24") (class "Default")
      (node (ref "JP4") (pin "7") (pinfunction "7_7") (pintype "passive"))
      (node (ref "SJ13") (pin "2") (pinfunction "2_2") (pintype "passive"))
      (node (ref "U2") (pin "D24") (pinfunction "D24_D24") (pintype "bidirectional"))
    )
    (net (code "37") (name "D25") (class "Default")
      (node (ref "JP4") (pin "8") (pinfunction "8_8") (pintype "passive"))
      (node (ref "SJ11") (pin "2") (pinfunction "2_2") (pintype "passive"))
      (node (ref "U2") (pin "D25") (pinfunction "D25_D25") (pintype "bidirectional"))
    )
    (net (code "38") (name "D26") (class "Default")
      (node (ref "JP4") (pin "9") (pinfunction "9_9") (pintype "passive"))
      (node (ref "U2") (pin "D26") (pinfunction "D26_D26") (pintype "bidirectional"))
    )
    (net (code "39") (name "D27") (class "Default")
      (node (ref "JP4") (pin "10") (pinfunction "10_10") (pintype "passive"))
      (node (ref "U2") (pin "D27") (pinfunction "D27_D27") (pintype "bidirectional"))
    )
    (net (code "40") (name "D28") (class "Default")
      (node (ref "JP4") (pin "11") (pinfunction "11_11") (pintype "passive"))
      (node (ref "U2") (pin "D28") (pinfunction "D28_D28") (pintype "bidirectional"))
    )
    (net (code "41") (name "D29") (class "Default")
      (node (ref "JP12") (pin "3") (pinfunction "3_3") (pintype "passive"))
      (node (ref "U2") (pin "D29") (pinfunction "D29_D29") (pintype "bidirectional"))
    )
    (net (code "42") (name "D30") (class "Default")
      (node (ref "JP12") (pin "4") (pinfunction "4_4") (pintype "passive"))
      (node (ref "U2") (pin "D30") (pinfunction "D30_D30") (pintype "bidirectional"))
    )
    (net (code "43") (name "D31") (class "Default")
      (node (ref "JP12") (pin "5") (pinfunction "5_5") (pintype "passive"))
      (node (ref "U2") (pin "D31") (pinfunction "D31_D31") (pintype "bidirectional"))
    )
    (net (code "44") (name "D32") (class "Default")
      (node (ref "JP12") (pin "6") (pinfunction "6_6") (pintype "passive"))
      (node (ref "U2") (pin "D32") (pinfunction "D32_D32") (pintype "bidirectional"))
    )
    (net (code "45") (name "D33") (class "Default")
      (node (ref "JP12") (pin "7") (pinfunction "7_7") (pintype "passive"))
      (node (ref "U2") (pin "D33") (pinfunction "D33_D33") (pintype "bidirectional"))
    )
    (net (code "46") (name "GND") (class "Default")
      (node (ref "BAT1") (pin "GND") (pinfunction "-_GND") (pintype "power_in"))
      (node (ref "C1") (pin "-") (pinfunction "2_-") (pintype "bidirectional"))
      (node (ref "C10") (pin "-") (pinfunction "2_-") (pintype "bidirectional"))
      (node (ref "C11") (pin "-") (pinfunction "2_-") (pintype "bidirectional"))
      (node (ref "C13") (pin "-") (pinfunction "2_-") (pintype "bidirectional"))
      (node (ref "C16") (pin "2") (pinfunction "2_2") (pintype "bidirectional"))
      (node (ref "C17") (pin "2") (pinfunction "2_2") (pintype "bidirectional"))
      (node (ref "C18") (pin "2") (pinfunction "2_2") (pintype "bidirectional"))
      (node (ref "C19") (pin "2") (pinfunction "2_2") (pintype "bidirectional"))
      (node (ref "C2") (pin "-") (pinfunction "2_-") (pintype "bidirectional"))
      (node (ref "C20") (pin "2") (pinfunction "2_2") (pintype "bidirectional"))
      (node (ref "C3") (pin "-") (pinfunction "2_-") (pintype "bidirectional"))
      (node (ref "C4") (pin "1") (pinfunction "1_1") (pintype "bidirectional"))
      (node (ref "C5") (pin "-") (pinfunction "2_-") (pintype "bidirectional"))
      (node (ref "C6") (pin "1") (pinfunction "1_1") (pintype "bidirectional"))
      (node (ref "C7") (pin "-") (pinfunction "2_-") (pintype "bidirectional"))
      (node (ref "C8") (pin "1") (pinfunction "1_1") (pintype "bidirectional"))
      (node (ref "C9") (pin "-") (pinfunction "2_-") (pintype "bidirectional"))
      (node (ref "D1") (pin "-") (pinfunction "-_-") (pintype "passive"))
      (node (ref "D3") (pin "1") (pinfunction "+_1") (pintype "passive"))
      (node (ref "D4") (pin "-") (pinfunction "-_-") (pintype "passive"))
      (node (ref "D5") (pin "-") (pinfunction "-_-") (pintype "passive"))
      (node (ref "J1") (pin "-1") (pinfunction "-_-1") (pintype "bidirectional"))
      (node (ref "J1") (pin "-2") (pinfunction "CDN_-2") (pintype "bidirectional"))
      (node (ref "J2") (pin "10") (pinfunction "10_10") (pintype "bidirectional"))
      (node (ref "J4") (pin "6") (pinfunction "VSS_6") (pintype "bidirectional"))
      (node (ref "J4") (pin "G1") (pinfunction "G1_G1") (pintype "bidirectional"))
      (node (ref "J4") (pin "G2") (pinfunction "G2_G2") (pintype "bidirectional"))
      (node (ref "J4") (pin "G3") (pinfunction "G3_G3") (pintype "bidirectional"))
      (node (ref "J4") (pin "G4") (pinfunction "G4_G4") (pintype "bidirectional"))
      (node (ref "J5") (pin "-") (pinfunction "-_-") (pintype "bidirectional"))
      (node (ref "J5") (pin "3") (pinfunction "3_3") (pintype "bidirectional"))
      (node (ref "J5") (pin "4") (pinfunction "4_4") (pintype "bidirectional"))
      (node (ref "J6") (pin "E1") (pinfunction "GND_E1") (pintype "bidirectional"))
      (node (ref "J6") (pin "E2") (pinfunction "GND_E2") (pintype "bidirectional"))
      (node (ref "J6") (pin "P1") (pinfunction "GND_P1") (pintype "bidirectional"))
      (node (ref "J6") (pin "P2") (pinfunction "GND_P2") (pintype "bidirectional"))
      (node (ref "JP12") (pin "1") (pinfunction "1_1") (pintype "passive"))
      (node (ref "JP4") (pin "13") (pinfunction "13_13") (pintype "passive"))
      (node (ref "JP5") (pin "7") (pinfunction "7_7") (pintype "passive"))
      (node (ref "JP6") (pin "2") (pinfunction "2_2") (pintype "passive"))
      (node (ref "JP6") (pin "3") (pinfunction "3_3") (pintype "passive"))
      (node (ref "JP9") (pin "6") (pinfunction "6_6") (pintype "passive"))
      (node (ref "K3") (pin "2") (pinfunction "2_2") (pintype "bidirectional"))
      (node (ref "K3") (pin "S1") (pinfunction "S1_S1") (pintype "bidirectional"))
      (node (ref "K3") (pin "S2") (pinfunction "S2_S2") (pintype "bidirectional"))
      (node (ref "K4") (pin "2") (pinfunction "2_2") (pintype "bidirectional"))
      (node (ref "K4") (pin "S1") (pinfunction "S1_S1") (pintype "bidirectional"))
      (node (ref "K4") (pin "S2") (pinfunction "S2_S2") (pintype "bidirectional"))
      (node (ref "L1") (pin "1") (pinfunction "1_1") (pintype "passive"))
      (node (ref "R27") (pin "1") (pinfunction "1_1") (pintype "bidirectional"))
      (node (ref "R30") (pin "1") (pinfunction "1_1") (pintype "bidirectional"))
      (node (ref "R35") (pin "1") (pinfunction "1_1") (pintype "bidirectional"))
      (node (ref "R38") (pin "2") (pinfunction "2_2") (pintype "bidirectional"))
      (node (ref "R39") (pin "2") (pinfunction "2_2") (pintype "bidirectional"))
      (node (ref "U1") (pin "1") (pinfunction "TEMP_1") (pintype "input"))
      (node (ref "U1") (pin "3") (pinfunction "GND_3") (pintype "power_in"))
      (node (ref "U1") (pin "HEAT") (pinfunction "H_HEAT") (pintype "bidirectional"))
      (node (ref "U2") (pin "GND_A") (pinfunction "GND_GND_A") (pintype "power_in"))
      (node (ref "U2") (pin "GND_B") (pinfunction "GND_GND_B") (pintype "power_in"))
      (node (ref "U2") (pin "GND_C") (pinfunction "GND_GND_C") (pintype "power_in"))
      (node (ref "U3") (pin "1") (pinfunction "GND_1") (pintype "bidirectional"))
      (node (ref "U4") (pin "1") (pinfunction "GND_1") (pintype "bidirectional"))
      (node (ref "U5") (pin "18") (pinfunction "GND_18") (pintype "input"))
      (node (ref "U5") (pin "21") (pinfunction "GND_21") (pintype "input"))
      (node (ref "U5") (pin "25") (pinfunction "GND_25") (pintype "input"))
      (node (ref "U5") (pin "26") (pinfunction "TEST_26") (pintype "input"))
      (node (ref "U5") (pin "7") (pinfunction "GND_7") (pintype "input"))
      (node (ref "U6") (pin "GND") (pinfunction "GND_GND") (pintype "power_in"))
    )
    (net (code "47") (name "Net-(C2-1)") (class "Default")
      (node (ref "C2") (pin "+") (pinfunction "1_+") (pintype "bidirectional"))
      (node (ref "SJ12") (pin "2") (pinfunction "2_2") (pintype "passive"))
      (node (ref "SV2") (pin "2") (pinfunction "2_2") (pintype "passive"))
      (node (ref "SV2") (pin "4") (pinfunction "4_4") (pintype "passive"))
      (node (ref "SV2") (pin "6") (pinfunction "6_6") (pintype "passive"))
      (node (ref "SV2") (pin "8") (pinfunction "8_8") (pintype "passive"))
      (node (ref "U3") (pin "2") (pinfunction "OUT_2") (pintype "bidirectional"))
      (node (ref "U3") (pin "TER") (pinfunction "OUT_TER") (pintype "bidirectional"))
    )
    (net (code "48") (name "Net-(C3-1)") (class "Default")
      (node (ref "C3") (pin "+") (pinfunction "1_+") (pintype "bidirectional"))
      (node (ref "SJ7") (pin "1") (pinfunction "1_1") (pintype "passive"))
      (node (ref "SV3") (pin "1") (pinfunction "1_1") (pintype "passive"))
      (node (ref "SV3") (pin "3") (pinfunction "3_3") (pintype "passive"))
      (node (ref "SV3") (pin "5") (pinfunction "5_5") (pintype "passive"))
      (node (ref "SV3") (pin "7") (pinfunction "7_7") (pintype "passive"))
      (node (ref "U4") (pin "3") (pinfunction "IN_3") (pintype "bidirectional"))
    )
    (net (code "49") (name "Net-(C7-1)") (class "Default")
      (node (ref "C7") (pin "+") (pinfunction "1_+") (pintype "bidirectional"))
      (node (ref "SJ7") (pin "2") (pinfunction "2_2") (pintype "passive"))
      (node (ref "SV1") (pin "2") (pinfunction "2_2") (pintype "passive"))
      (node (ref "SV1") (pin "4") (pinfunction "4_4") (pintype "passive"))
      (node (ref "SV1") (pin "6") (pinfunction "6_6") (pintype "passive"))
      (node (ref "SV1") (pin "8") (pinfunction "8_8") (pintype "passive"))
      (node (ref "U4") (pin "2") (pinfunction "OUT_2") (pintype "bidirectional"))
      (node (ref "U4") (pin "TER") (pinfunction "OUT_TER") (pintype "bidirectional"))
    )
    (net (code "50") (name "Net-(D1-Pad+)") (class "Default")
      (node (ref "D1") (pin "+") (pinfunction "+_+") (pintype "passive"))
      (node (ref "R31") (pin "1") (pinfunction "1_1") (pintype "bidirectional"))
    )
    (net (code "51") (name "Net-(D4-Pad+)") (class "Default")
      (node (ref "D4") (pin "+") (pinfunction "+_+") (pintype "passive"))
      (node (ref "R32") (pin "1") (pinfunction "1_1") (pintype "bidirectional"))
    )
    (net (code "52") (name "Net-(D5-Pad+)") (class "Default")
      (node (ref "D5") (pin "+") (pinfunction "+_+") (pintype "passive"))
      (node (ref "R33") (pin "1") (pinfunction "1_1") (pintype "bidirectional"))
    )
    (net (code "53") (name "Net-(D6-Pad-)") (class "Default")
      (node (ref "D6") (pin "-") (pinfunction "-_-") (pintype "passive"))
      (node (ref "R26") (pin "2") (pinfunction "2_2") (pintype "bidirectional"))
    )
    (net (code "54") (name "Net-(D7-Pad-)") (class "Default")
      (node (ref "D7") (pin "-") (pinfunction "-_-") (pintype "passive"))
      (node (ref "R30") (pin "2") (pinfunction "2_2") (pintype "bidirectional"))
    )
    (net (code "55") (name "Net-(D8-Pad+)") (class "Default")
      (node (ref "D8") (pin "+") (pinfunction "+_+") (pintype "passive"))
      (node (ref "D9") (pin "+") (pinfunction "+_+") (pintype "passive"))
      (node (ref "R28") (pin "2") (pinfunction "2_2") (pintype "bidirectional"))
    )
    (net (code "56") (name "Net-(D12-Pad+)") (class "Default")
      (node (ref "D12") (pin "+") (pinfunction "+_+") (pintype "passive"))
      (node (ref "R36") (pin "1") (pinfunction "1_1") (pintype "bidirectional"))
    )
    (net (code "57") (name "Net-(D13-Pad+)") (class "Default")
      (node (ref "D13") (pin "+") (pinfunction "+_+") (pintype "passive"))
      (node (ref "R37") (pin "1") (pinfunction "1_1") (pintype "bidirectional"))
    )
    (net (code "58") (name "Net-(D14-Pad+)") (class "Default")
      (node (ref "D14") (pin "+") (pinfunction "+_+") (pintype "passive"))
      (node (ref "F2") (pin "2") (pinfunction "2_2") (pintype "bidirectional"))
    )
    (net (code "59") (name "Net-(F2-Pad1)") (class "Default")
      (node (ref "F2") (pin "1") (pinfunction "1_1") (pintype "bidirectional"))
      (node (ref "SJ19") (pin "1") (pinfunction "1_1") (pintype "passive"))
    )
    (net (code "60") (name "Net-(J2-Pad5)") (class "Default")
      (node (ref "J2") (pin "5") (pinfunction "5_5") (pintype "bidirectional"))
      (node (ref "R3") (pin "1") (pinfunction "1_1") (pintype "bidirectional"))
      (node (ref "SJ2") (pin "1") (pinfunction "1_1") (pintype "passive"))
    )
    (net (code "61") (name "Net-(J2-Pad6)") (class "Default")
      (node (ref "J2") (pin "6") (pinfunction "6_6") (pintype "bidirectional"))
      (node (ref "R31") (pin "2") (pinfunction "2_2") (pintype "bidirectional"))
    )
    (net (code "62") (name "Net-(J3-Pad3)") (class "Default")
      (node (ref "J3") (pin "3") (pinfunction "3_3") (pintype "bidirectional"))
      (node (ref "R32") (pin "2") (pinfunction "2_2") (pintype "bidirectional"))
    )
    (net (code "63") (name "Net-(J3-Pad5)") (class "Default")
      (node (ref "J3") (pin "5") (pinfunction "5_5") (pintype "bidirectional"))
      (node (ref "R33") (pin "2") (pinfunction "2_2") (pintype "bidirectional"))
    )
    (net (code "64") (name "Net-(J4-CDN)") (class "Default")
      (node (ref "J4") (pin "9") (pinfunction "CDN_9") (pintype "bidirectional"))
      (node (ref "SJ8") (pin "2") (pinfunction "2_2") (pintype "passive"))
    )
    (net (code "65") (name "Net-(J4-CS)") (class "Default")
      (node (ref "J4") (pin "2") (pinfunction "CS_2") (pintype "bidirectional"))
      (node (ref "SJ4") (pin "2") (pinfunction "2_2") (pintype "passive"))
    )
    (net (code "66") (name "Net-(J6-DM)") (class "Default")
      (node (ref "J6") (pin "2") (pinfunction "DM_2") (pintype "bidirectional"))
      (node (ref "U5") (pin "16") (pinfunction "USBDM_16") (pintype "input"))
    )
    (net (code "67") (name "Net-(J6-DP)") (class "Default")
      (node (ref "J6") (pin "3") (pinfunction "DP_3") (pintype "bidirectional"))
      (node (ref "U5") (pin "15") (pinfunction "USBDP_15") (pintype "input"))
    )
    (net (code "68") (name "Net-(J6-GND-Pad5)") (class "Default")
      (node (ref "J6") (pin "5") (pinfunction "GND_5") (pintype "bidirectional"))
      (node (ref "L1") (pin "2") (pinfunction "2_2") (pintype "passive"))
    )
    (net (code "69") (name "Net-(J6-VCC)") (class "Default")
      (node (ref "J6") (pin "1") (pinfunction "VCC_1") (pintype "bidirectional"))
      (node (ref "L2") (pin "1") (pinfunction "1_1") (pintype "passive"))
    )
    (net (code "70") (name "Net-(PAD1-P)") (class "Default")
      (node (ref "JP11") (pin "1") (pinfunction "1_1") (pintype "passive"))
      (node (ref "PAD1") (pin "1") (pinfunction "P_1") (pintype "passive"))
    )
    (net (code "71") (name "Net-(PAD2-P)") (class "Default")
      (node (ref "JP11") (pin "2") (pinfunction "2_2") (pintype "passive"))
      (node (ref "PAD2") (pin "1") (pinfunction "P_1") (pintype "passive"))
    )
    (net (code "72") (name "Net-(PAD3-P)") (class "Default")
      (node (ref "JP11") (pin "3") (pinfunction "3_3") (pintype "passive"))
      (node (ref "PAD3") (pin "1") (pinfunction "P_1") (pintype "passive"))
    )
    (net (code "73") (name "Net-(PAD4-P)") (class "Default")
      (node (ref "JP11") (pin "4") (pinfunction "4_4") (pintype "passive"))
      (node (ref "PAD4") (pin "1") (pinfunction "P_1") (pintype "passive"))
    )
    (net (code "74") (name "Net-(PAD6-P)") (class "Default")
      (node (ref "PAD6") (pin "1") (pinfunction "P_1") (pintype "passive"))
      (node (ref "SJ10") (pin "2") (pinfunction "2_2") (pintype "passive"))
      (node (ref "U2") (pin "AREF") (pinfunction "AREF_AREF") (pintype "input"))
    )
    (net (code "75") (name "Net-(Q1-D)") (class "Default")
      (node (ref "Q1") (pin "3") (pinfunction "D_3") (pintype "passive"))
      (node (ref "SJ9") (pin "2") (pinfunction "2_2") (pintype "passive"))
    )
    (net (code "76") (name "Net-(Q1-G)") (class "Default")
      (node (ref "D10") (pin "+") (pinfunction "+_+") (pintype "passive"))
      (node (ref "J7") (pin "4") (pinfunction "4_4") (pintype "bidirectional"))
      (node (ref "J7") (pin "5") (pinfunction "5_5") (pintype "bidirectional"))
      (node (ref "J7") (pin "6") (pinfunction "6_6") (pintype "bidirectional"))
      (node (ref "Q1") (pin "1") (pinfunction "G_1") (pintype "passive"))
      (node (ref "R27") (pin "2") (pinfunction "2_2") (pintype "bidirectional"))
    )
    (net (code "77") (name "Net-(Q1-S)") (class "Default")
      (node (ref "D10") (pin "-") (pinfunction "-_-") (pintype "passive"))
      (node (ref "Q1") (pin "2") (pinfunction "S_2") (pintype "passive"))
      (node (ref "R28") (pin "1") (pinfunction "1_1") (pintype "bidirectional"))
      (node (ref "U1") (pin "4") (pinfunction "VIN_4") (pintype "input"))
    )
    (net (code "78") (name "Net-(R1-Pad2)") (class "Default")
      (node (ref "R1") (pin "2") (pinfunction "2_2") (pintype "bidirectional"))
      (node (ref "SJ5") (pin "1") (pinfunction "1_1") (pintype "passive"))
    )
    (net (code "79") (name "Net-(R2-Pad2)") (class "Default")
      (node (ref "R2") (pin "2") (pinfunction "2_2") (pintype "bidirectional"))
      (node (ref "SJ6") (pin "1") (pinfunction "1_1") (pintype "passive"))
    )
    (net (code "80") (name "Net-(R4-Pad2)") (class "Default")
      (node (ref "R4") (pin "2") (pinfunction "2_2") (pintype "bidirectional"))
      (node (ref "SJ3") (pin "2") (pinfunction "2_2") (pintype "passive"))
      (node (ref "SJ8") (pin "1") (pinfunction "1_1") (pintype "passive"))
    )
    (net (code "81") (name "Net-(R5-Pad1)") (class "Default")
      (node (ref "R5") (pin "1") (pinfunction "1_1") (pintype "bidirectional"))
      (node (ref "U2") (pin "D8") (pinfunction "D8_D8") (pintype "bidirectional"))
    )
    (net (code "82") (name "Net-(R6-Pad1)") (class "Default")
      (node (ref "R6") (pin "1") (pinfunction "1_1") (pintype "bidirectional"))
      (node (ref "U2") (pin "D9") (pinfunction "D9_D9") (pintype "bidirectional"))
    )
    (net (code "83") (name "Net-(R7-Pad1)") (class "Default")
      (node (ref "R7") (pin "1") (pinfunction "1_1") (pintype "bidirectional"))
      (node (ref "U2") (pin "D10") (pinfunction "D10_D10") (pintype "bidirectional"))
    )
    (net (code "84") (name "Net-(R8-Pad1)") (class "Default")
      (node (ref "R8") (pin "1") (pinfunction "1_1") (pintype "bidirectional"))
      (node (ref "U2") (pin "D11") (pinfunction "D11_D11") (pintype "bidirectional"))
    )
    (net (code "85") (name "Net-(R9-Pad1)") (class "Default")
      (node (ref "R9") (pin "1") (pinfunction "1_1") (pintype "bidirectional"))
      (node (ref "U2") (pin "D12") (pinfunction "D12_D12") (pintype "bidirectional"))
    )
    (net (code "86") (name "Net-(R10-Pad2)") (class "Default")
      (node (ref "R10") (pin "2") (pinfunction "2_2") (pintype "bidirectional"))
      (node (ref "U2") (pin "A5") (pinfunction "A5_A5") (pintype "bidirectional"))
    )
    (net (code "87") (name "Net-(R11-Pad2)") (class "Default")
      (node (ref "R11") (pin "2") (pinfunction "2_2") (pintype "bidirectional"))
      (node (ref "U2") (pin "A4") (pinfunction "A4_A4") (pintype "bidirectional"))
    )
    (net (code "88") (name "Net-(R12-Pad2)") (class "Default")
      (node (ref "R12") (pin "2") (pinfunction "2_2") (pintype "bidirectional"))
      (node (ref "U2") (pin "A3") (pinfunction "A3_A3") (pintype "bidirectional"))
    )
    (net (code "89") (name "Net-(R13-Pad1)") (class "Default")
      (node (ref "R13") (pin "1") (pinfunction "1_1") (pintype "bidirectional"))
      (node (ref "U2") (pin "D0") (pinfunction "D0_D0") (pintype "bidirectional"))
    )
    (net (code "90") (name "Net-(R14-Pad1)") (class "Default")
      (node (ref "R14") (pin "1") (pinfunction "1_1") (pintype "bidirectional"))
      (node (ref "U2") (pin "D1") (pinfunction "D1_D1") (pintype "bidirectional"))
    )
    (net (code "91") (name "Net-(R15-Pad1)") (class "Default")
      (node (ref "R15") (pin "1") (pinfunction "1_1") (pintype "bidirectional"))
      (node (ref "U2") (pin "D2") (pinfunction "D2_D2") (pintype "bidirectional"))
    )
    (net (code "92") (name "Net-(R16-Pad1)") (class "Default")
      (node (ref "R16") (pin "1") (pinfunction "1_1") (pintype "bidirectional"))
      (node (ref "U2") (pin "D3") (pinfunction "D3_D3") (pintype "bidirectional"))
    )
    (net (code "93") (name "Net-(R17-Pad1)") (class "Default")
      (node (ref "R17") (pin "1") (pinfunction "1_1") (pintype "bidirectional"))
      (node (ref "U2") (pin "D4") (pinfunction "D4_D4") (pintype "bidirectional"))
    )
    (net (code "94") (name "Net-(R18-Pad1)") (class "Default")
      (node (ref "R18") (pin "1") (pinfunction "1_1") (pintype "bidirectional"))
      (node (ref "U2") (pin "D5") (pinfunction "D5_D5") (pintype "bidirectional"))
    )
    (net (code "95") (name "Net-(R19-Pad1)") (class "Default")
      (node (ref "R19") (pin "1") (pinfunction "1_1") (pintype "bidirectional"))
      (node (ref "U2") (pin "D6") (pinfunction "D6_D6") (pintype "bidirectional"))
    )
    (net (code "96") (name "Net-(R20-Pad1)") (class "Default")
      (node (ref "R20") (pin "1") (pinfunction "1_1") (pintype "bidirectional"))
      (node (ref "U2") (pin "D7") (pinfunction "D7_D7") (pintype "bidirectional"))
    )
    (net (code "97") (name "Net-(R21-Pad2)") (class "Default")
      (node (ref "R21") (pin "2") (pinfunction "2_2") (pintype "bidirectional"))
      (node (ref "U2") (pin "A2") (pinfunction "A2_A2") (pintype "bidirectional"))
    )
    (net (code "98") (name "Net-(R22-Pad2)") (class "Default")
      (node (ref "R22") (pin "2") (pinfunction "2_2") (pintype "bidirectional"))
      (node (ref "U2") (pin "A1") (pinfunction "A1_A1") (pintype "bidirectional"))
    )
    (net (code "99") (name "Net-(R23-Pad2)") (class "Default")
      (node (ref "R23") (pin "2") (pinfunction "2_2") (pintype "bidirectional"))
      (node (ref "U2") (pin "A0") (pinfunction "A0_A0") (pintype "bidirectional"))
    )
    (net (code "100") (name "Net-(R24-Pad1)") (class "Default")
      (node (ref "R24") (pin "1") (pinfunction "1_1") (pintype "bidirectional"))
      (node (ref "U2") (pin "D13") (pinfunction "D13_D13") (pintype "bidirectional"))
    )
    (net (code "101") (name "Net-(R26-Pad1)") (class "Default")
      (node (ref "R26") (pin "1") (pinfunction "1_1") (pintype "bidirectional"))
      (node (ref "SJ8") (pin "3") (pinfunction "3_3") (pintype "passive"))
    )
    (net (code "102") (name "Net-(R34-Pad1)") (class "Default")
      (node (ref "R34") (pin "1") (pinfunction "1_1") (pintype "bidirectional"))
      (node (ref "R35") (pin "2") (pinfunction "2_2") (pintype "bidirectional"))
    )
    (net (code "103") (name "Net-(U1-CHRG)") (class "Default")
      (node (ref "D8") (pin "-") (pinfunction "-_-") (pintype "passive"))
      (node (ref "U1") (pin "7") (pinfunction "CHRG_7") (pintype "bidirectional"))
    )
    (net (code "104") (name "Net-(U1-DONE)") (class "Default")
      (node (ref "D9") (pin "-") (pinfunction "-_-") (pintype "passive"))
      (node (ref "U1") (pin "6") (pinfunction "DONE_6") (pintype "bidirectional"))
    )
    (net (code "105") (name "Net-(U1-ISET)") (class "Default")
      (node (ref "R34") (pin "2") (pinfunction "2_2") (pintype "bidirectional"))
      (node (ref "U1") (pin "2") (pinfunction "ISET_2") (pintype "bidirectional"))
    )
    (net (code "106") (name "Net-(U5-3V3OUT)") (class "Default")
      (node (ref "C16") (pin "1") (pinfunction "1_1") (pintype "bidirectional"))
      (node (ref "U5") (pin "17") (pinfunction "3V3OUT_17") (pintype "input"))
    )
    (net (code "107") (name "Net-(U5-CBUS0)") (class "Default")
      (node (ref "D12") (pin "-") (pinfunction "-_-") (pintype "passive"))
      (node (ref "U5") (pin "23") (pinfunction "CBUS0_23") (pintype "input"))
    )
    (net (code "108") (name "Net-(U5-CBUS1)") (class "Default")
      (node (ref "D13") (pin "-") (pinfunction "-_-") (pintype "passive"))
      (node (ref "U5") (pin "22") (pinfunction "CBUS1_22") (pintype "input"))
    )
    (net (code "109") (name "Net-(U5-CBUS3)") (class "Default")
      (node (ref "R40") (pin "1") (pinfunction "1_1") (pintype "bidirectional"))
      (node (ref "SJ17") (pin "1") (pinfunction "1_1") (pintype "passive"))
      (node (ref "U5") (pin "14") (pinfunction "CBUS3_14") (pintype "input"))
    )
    (net (code "110") (name "Net-(U5-RXD)") (class "Default")
      (node (ref "SJ16") (pin "2") (pinfunction "2_2") (pintype "passive"))
      (node (ref "U5") (pin "5") (pinfunction "RXD_5") (pintype "input"))
    )
    (net (code "111") (name "Net-(U5-TXD)") (class "Default")
      (node (ref "SJ14") (pin "2") (pinfunction "2_2") (pintype "passive"))
      (node (ref "U5") (pin "1") (pinfunction "TXD_1") (pintype "input"))
    )
    (net (code "112") (name "Net-(U5-VCC)") (class "Default")
      (node (ref "C18") (pin "1") (pinfunction "1_1") (pintype "bidirectional"))
      (node (ref "C19") (pin "1") (pinfunction "1_1") (pintype "bidirectional"))
      (node (ref "C20") (pin "1") (pinfunction "1_1") (pintype "bidirectional"))
      (node (ref "D11") (pin "+") (pinfunction "+_+") (pintype "passive"))
      (node (ref "L2") (pin "2") (pinfunction "2_2") (pintype "passive"))
      (node (ref "U5") (pin "20") (pinfunction "VCC_20") (pintype "input"))
    )
    (net (code "113") (name "Net-(U5-~{CTS})") (class "Default")
      (node (ref "R38") (pin "1") (pinfunction "1_1") (pintype "bidirectional"))
      (node (ref "U5") (pin "11") (pinfunction "~{CTS}_11") (pintype "input"))
    )
    (net (code "114") (name "Net-(U5-~{DSR})") (class "Default")
      (node (ref "R39") (pin "1") (pinfunction "1_1") (pintype "bidirectional"))
      (node (ref "U5") (pin "9") (pinfunction "~{DSR}_9") (pintype "input"))
    )
    (net (code "115") (name "PROG") (class "Default")
      (node (ref "JP12") (pin "2") (pinfunction "2_2") (pintype "passive"))
      (node (ref "K3") (pin "1") (pinfunction "1_1") (pintype "bidirectional"))
      (node (ref "R25") (pin "1") (pinfunction "1_1") (pintype "bidirectional"))
      (node (ref "U2") (pin "PROG") (pinfunction "PROGRAM_PROG") (pintype "input"))
    )
    (net (code "116") (name "RESET") (class "Default")
      (node (ref "JP6") (pin "6") (pinfunction "6_6") (pintype "passive"))
      (node (ref "K4") (pin "1") (pinfunction "1_1") (pintype "bidirectional"))
      (node (ref "R29") (pin "1") (pinfunction "1_1") (pintype "bidirectional"))
      (node (ref "U2") (pin "RESET") (pinfunction "RESET_RESET") (pintype "input"))
      (node (ref "U5") (pin "19") (pinfunction "~{RESET}_19") (pintype "input"))
    )
    (net (code "117") (name "RF_CE") (class "Default")
      (node (ref "SJ13") (pin "1") (pinfunction "1_1") (pintype "passive"))
      (node (ref "U6") (pin "CE") (pinfunction "CE_CE") (pintype "bidirectional"))
    )
    (net (code "118") (name "RF_CS") (class "Default")
      (node (ref "SJ11") (pin "1") (pinfunction "1_1") (pintype "passive"))
      (node (ref "U6") (pin "CS") (pinfunction "CS_CS") (pintype "input"))
    )
    (net (code "119") (name "T3_VIN") (class "Default")
      (node (ref "D2") (pin "+") (pinfunction "+_+") (pintype "passive"))
      (node (ref "SJ15") (pin "2") (pinfunction "2_2") (pintype "passive"))
      (node (ref "SV1") (pin "3") (pinfunction "3_3") (pintype "passive"))
      (node (ref "SV2") (pin "1") (pinfunction "1_1") (pintype "passive"))
    )
    (net (code "120") (name "VBAT") (class "Default")
      (node (ref "BAT1") (pin "PWR@1") (pinfunction "+_PWR@1") (pintype "power_in"))
      (node (ref "JP4") (pin "12") (pinfunction "12_12") (pintype "passive"))
      (node (ref "U2") (pin "VBAT") (pinfunction "VBAT_VBAT") (pintype "power_in"))
    )
    (net (code "121") (name "VCC") (class "Default")
      (node (ref "C1") (pin "+") (pinfunction "1_+") (pintype "bidirectional"))
      (node (ref "C5") (pin "+") (pinfunction "1_+") (pintype "bidirectional"))
      (node (ref "D3") (pin "2") (pinfunction "-_2") (pintype "passive"))
      (node (ref "F1") (pin "2") (pinfunction "2_2") (pintype "bidirectional"))
      (node (ref "J7") (pin "3") (pinfunction "3_3") (pintype "bidirectional"))
      (node (ref "SJ1") (pin "1") (pinfunction "1_1") (pintype "passive"))
      (node (ref "SJ12") (pin "1") (pinfunction "1_1") (pintype "passive"))
      (node (ref "SV3") (pin "2") (pinfunction "2_2") (pintype "passive"))
      (node (ref "U3") (pin "3") (pinfunction "IN_3") (pintype "bidirectional"))
    )
    (net (code "122") (name "VIN_T3_DIRECT") (class "Default")
      (node (ref "D14") (pin "-") (pinfunction "-_-") (pintype "passive"))
      (node (ref "D2") (pin "-") (pinfunction "-_-") (pintype "passive"))
      (node (ref "SJ15") (pin "1") (pinfunction "1_1") (pintype "passive"))
      (node (ref "SJ18") (pin "1") (pinfunction "1_1") (pintype "passive"))
      (node (ref "U2") (pin "VIN") (pinfunction "VIN_VIN") (pintype "power_in"))
    )
    (net (code "123") (name "VUSB") (class "Default")
      (node (ref "JP12") (pin "12") (pinfunction "12_12") (pintype "passive"))
      (node (ref "SJ18") (pin "2") (pinfunction "2_2") (pintype "passive"))
      (node (ref "SJ19") (pin "2") (pinfunction "2_2") (pintype "passive"))
      (node (ref "SJ9") (pin "1") (pinfunction "1_1") (pintype "passive"))
      (node (ref "U2") (pin "VUSB") (pinfunction "VUSB_VUSB") (pintype "power_in"))
    )
    (net (code "124") (name "unconnected-(J2-Pad4)") (class "Default")
      (node (ref "J2") (pin "4") (pinfunction "4_4") (pintype "bidirectional"))
    )
    (net (code "125") (name "unconnected-(J2-Pad7)") (class "Default")
      (node (ref "J2") (pin "7") (pinfunction "7_7") (pintype "bidirectional"))
    )
    (net (code "126") (name "unconnected-(J2-Pad8)") (class "Default")
      (node (ref "J2") (pin "8") (pinfunction "8_8") (pintype "bidirectional"))
    )
    (net (code "127") (name "unconnected-(J2-Pad9)") (class "Default")
      (node (ref "J2") (pin "9") (pinfunction "9_9") (pintype "bidirectional"))
    )
    (net (code "128") (name "unconnected-(J3-Pad1)") (class "Default")
      (node (ref "J3") (pin "1") (pinfunction "1_1") (pintype "bidirectional"))
    )
    (net (code "129") (name "unconnected-(J3-Pad2)") (class "Default")
      (node (ref "J3") (pin "2") (pinfunction "2_2") (pintype "bidirectional"))
    )
    (net (code "130") (name "unconnected-(J3-Pad4)") (class "Default")
      (node (ref "J3") (pin "4") (pinfunction "4_4") (pintype "bidirectional"))
    )
    (net (code "131") (name "unconnected-(J3-Pad6)") (class "Default")
      (node (ref "J3") (pin "6") (pinfunction "6_6") (pintype "bidirectional"))
    )
    (net (code "132") (name "unconnected-(J3-Pad7)") (class "Default")
      (node (ref "J3") (pin "7") (pinfunction "7_7") (pintype "bidirectional"))
    )
    (net (code "133") (name "unconnected-(J3-Pad8)") (class "Default")
      (node (ref "J3") (pin "8") (pinfunction "8_8") (pintype "bidirectional"))
    )
    (net (code "134") (name "unconnected-(J3-Pad9)") (class "Default")
      (node (ref "J3") (pin "9") (pinfunction "9_9") (pintype "bidirectional"))
    )
    (net (code "135") (name "unconnected-(J3-Pad10)") (class "Default")
      (node (ref "J3") (pin "10") (pinfunction "10_10") (pintype "bidirectional"))
    )
    (net (code "136") (name "unconnected-(J4-DATA1-Pad8)") (class "Default")
      (node (ref "J4") (pin "8") (pinfunction "DATA1_8") (pintype "bidirectional"))
    )
    (net (code "137") (name "unconnected-(J4-DATA2-Pad1)") (class "Default")
      (node (ref "J4") (pin "1") (pinfunction "DATA2_1") (pintype "bidirectional"))
    )
    (net (code "138") (name "unconnected-(J6-ID-Pad4)") (class "Default")
      (node (ref "J6") (pin "4") (pinfunction "ID_4") (pintype "bidirectional"))
    )
    (net (code "139") (name "unconnected-(JP6-Pad8)") (class "Default")
      (node (ref "JP6") (pin "8") (pinfunction "8_8") (pintype "passive"))
    )
    (net (code "140") (name "unconnected-(JP9-Pad2)") (class "Default")
      (node (ref "JP9") (pin "2") (pinfunction "2_2") (pintype "passive"))
    )
    (net (code "141") (name "unconnected-(JP9-Pad5)") (class "Default")
      (node (ref "JP9") (pin "5") (pinfunction "5_5") (pintype "passive"))
    )
    (net (code "142") (name "unconnected-(U5-CBUS2-Pad13)") (class "Default")
      (node (ref "U5") (pin "13") (pinfunction "CBUS2_13") (pintype "input"))
    )
    (net (code "143") (name "unconnected-(U5-CBUS4-Pad12)") (class "Default")
      (node (ref "U5") (pin "12") (pinfunction "CBUS4_12") (pintype "input"))
    )
    (net (code "144") (name "unconnected-(U5-OSCI-Pad27)") (class "Default")
      (node (ref "U5") (pin "27") (pinfunction "OSCI_27") (pintype "input"))
    )
    (net (code "145") (name "unconnected-(U5-OSCO-Pad28)") (class "Default")
      (node (ref "U5") (pin "28") (pinfunction "OSCO_28") (pintype "input"))
    )
    (net (code "146") (name "unconnected-(U5-~{DCD}-Pad10)") (class "Default")
      (node (ref "U5") (pin "10") (pinfunction "~{DCD}_10") (pintype "input"))
    )
    (net (code "147") (name "unconnected-(U5-~{DTR}-Pad2)") (class "Default")
      (node (ref "U5") (pin "2") (pinfunction "~{DTR}_2") (pintype "input"))
    )
    (net (code "148") (name "unconnected-(U5-~{RI}-Pad6)") (class "Default")
      (node (ref "U5") (pin "6") (pinfunction "~{RI}_6") (pintype "input"))
    )
    (net (code "149") (name "unconnected-(U5-~{RTS}-Pad3)") (class "Default")
      (node (ref "U5") (pin "3") (pinfunction "~{RTS}_3") (pintype "input"))
    )
  )
)
